# LR1302_LoRaWAN_Gateway_Module_V1_0_868US.net
KiCad netlist of a schematic drawn in EAGLE
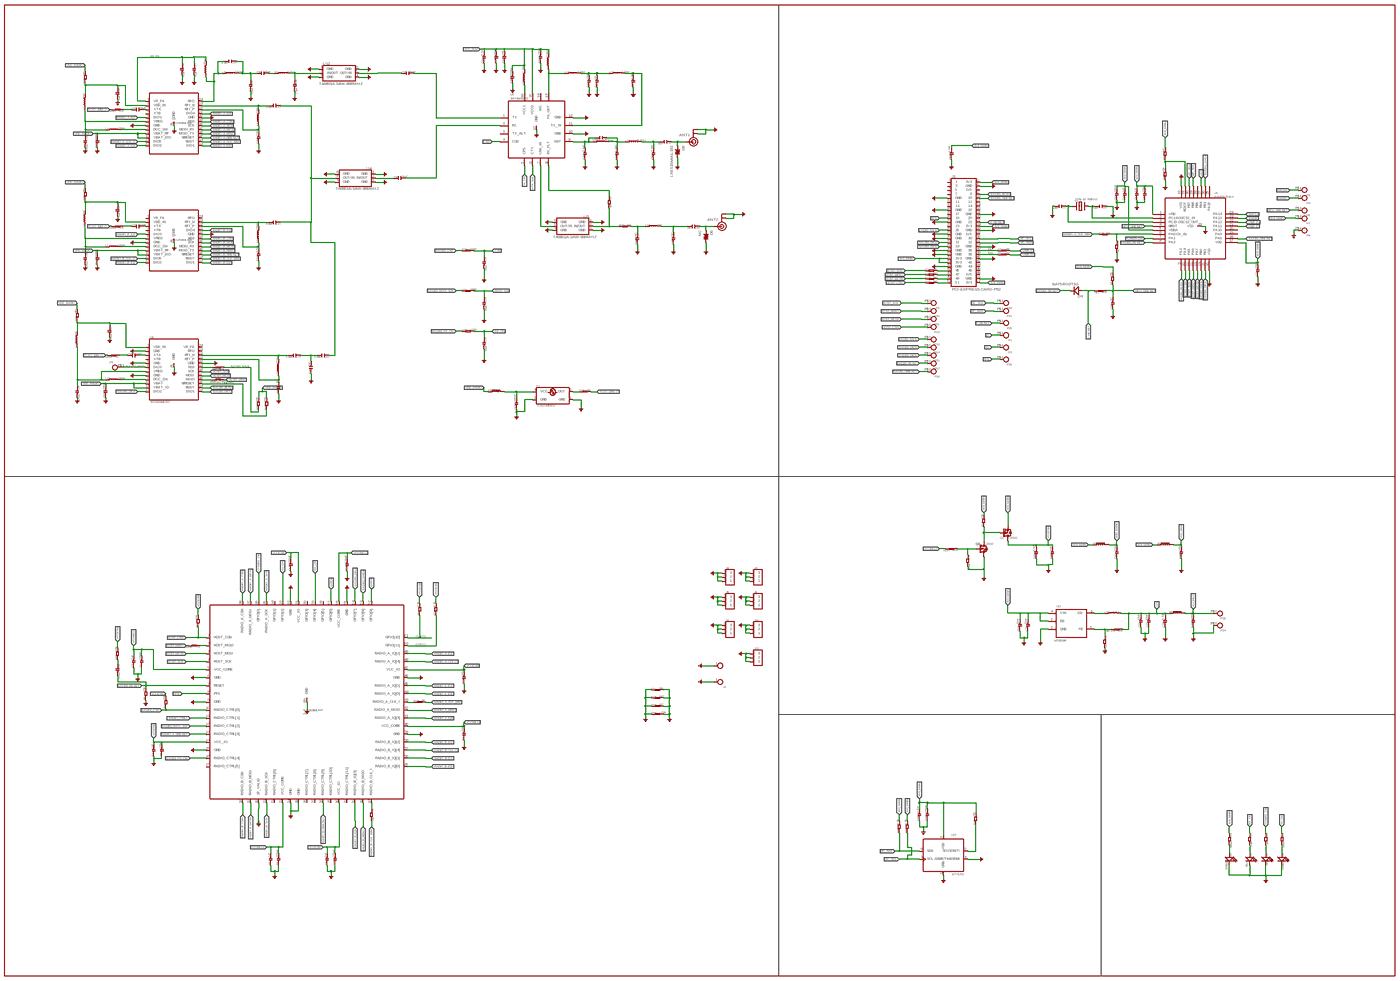
[diagram p0: schematic, sheet 1, overview]
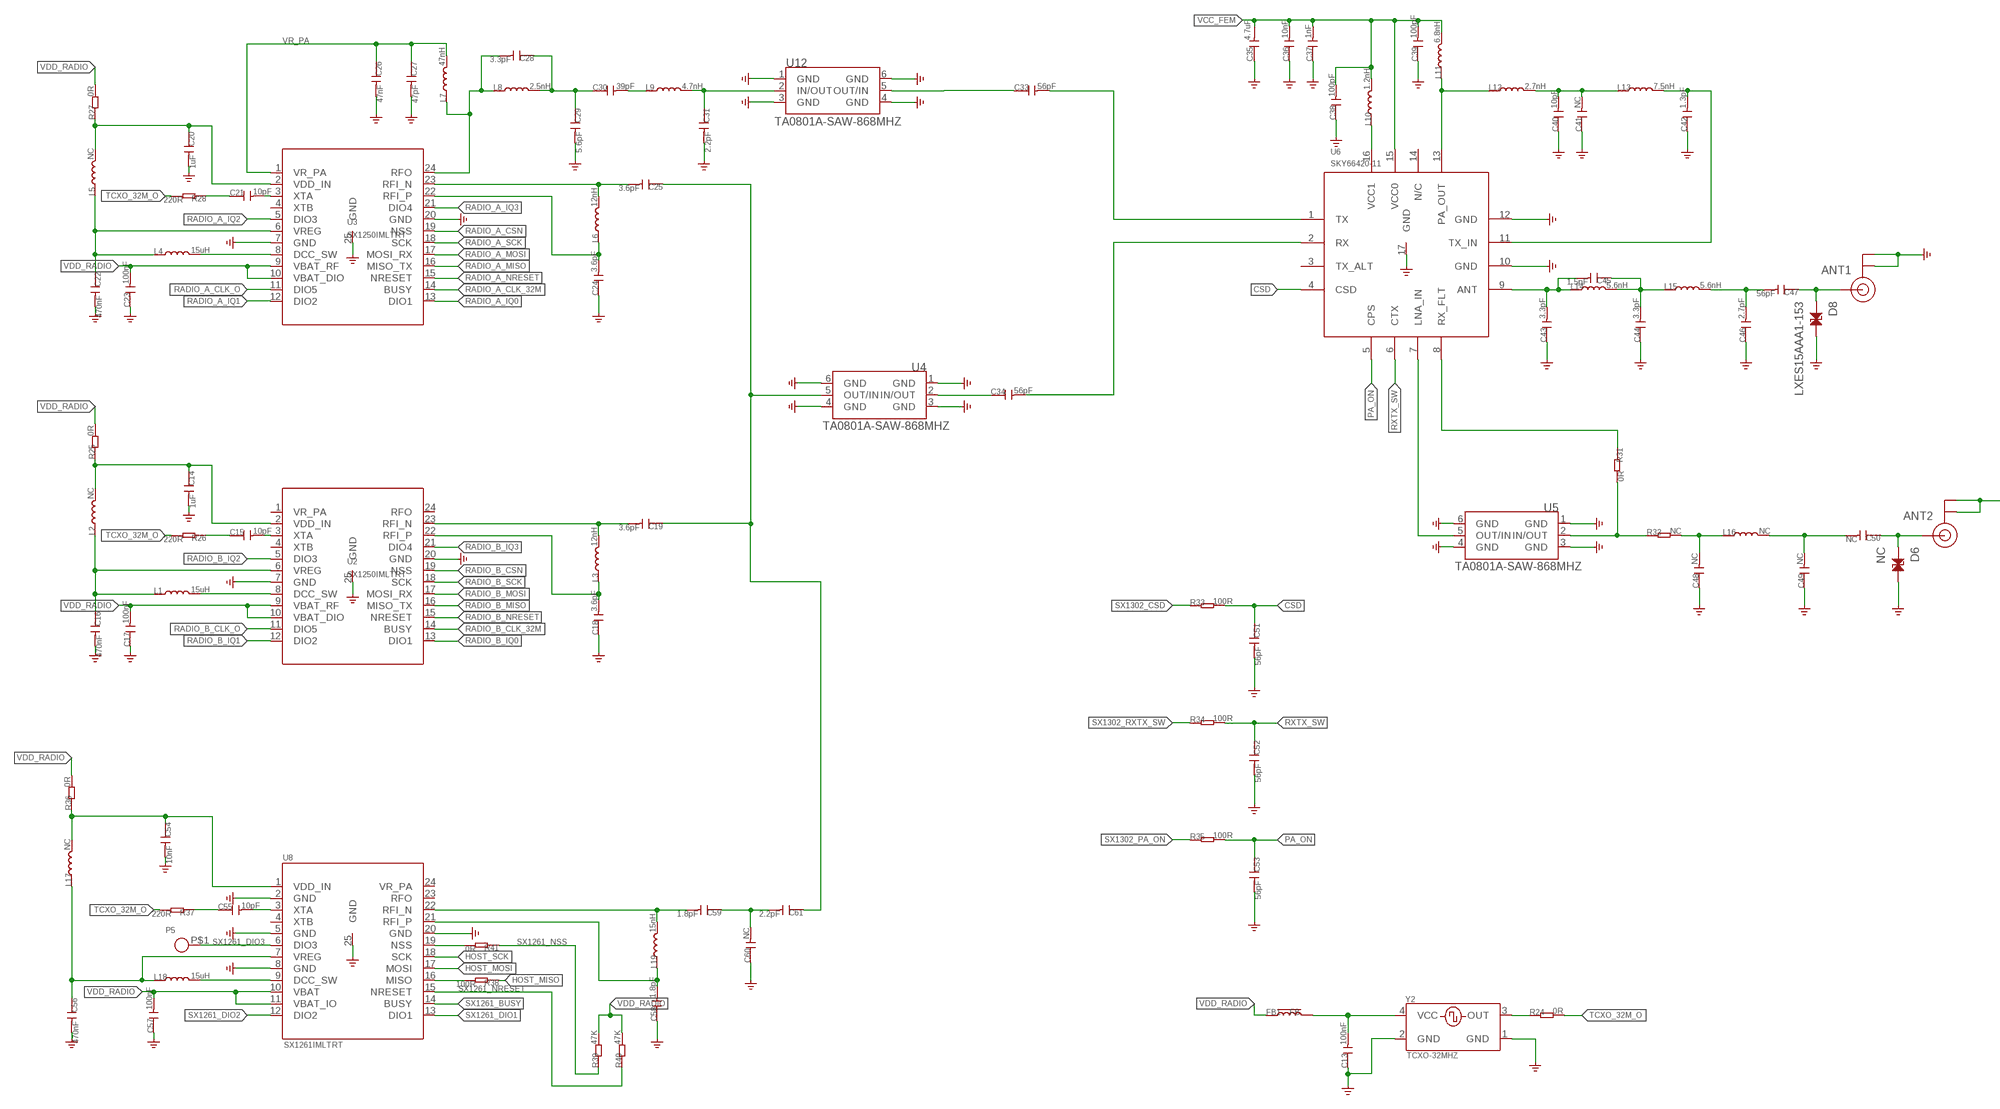
[diagram p1: schematic, sheet 1, part 1 of 4]
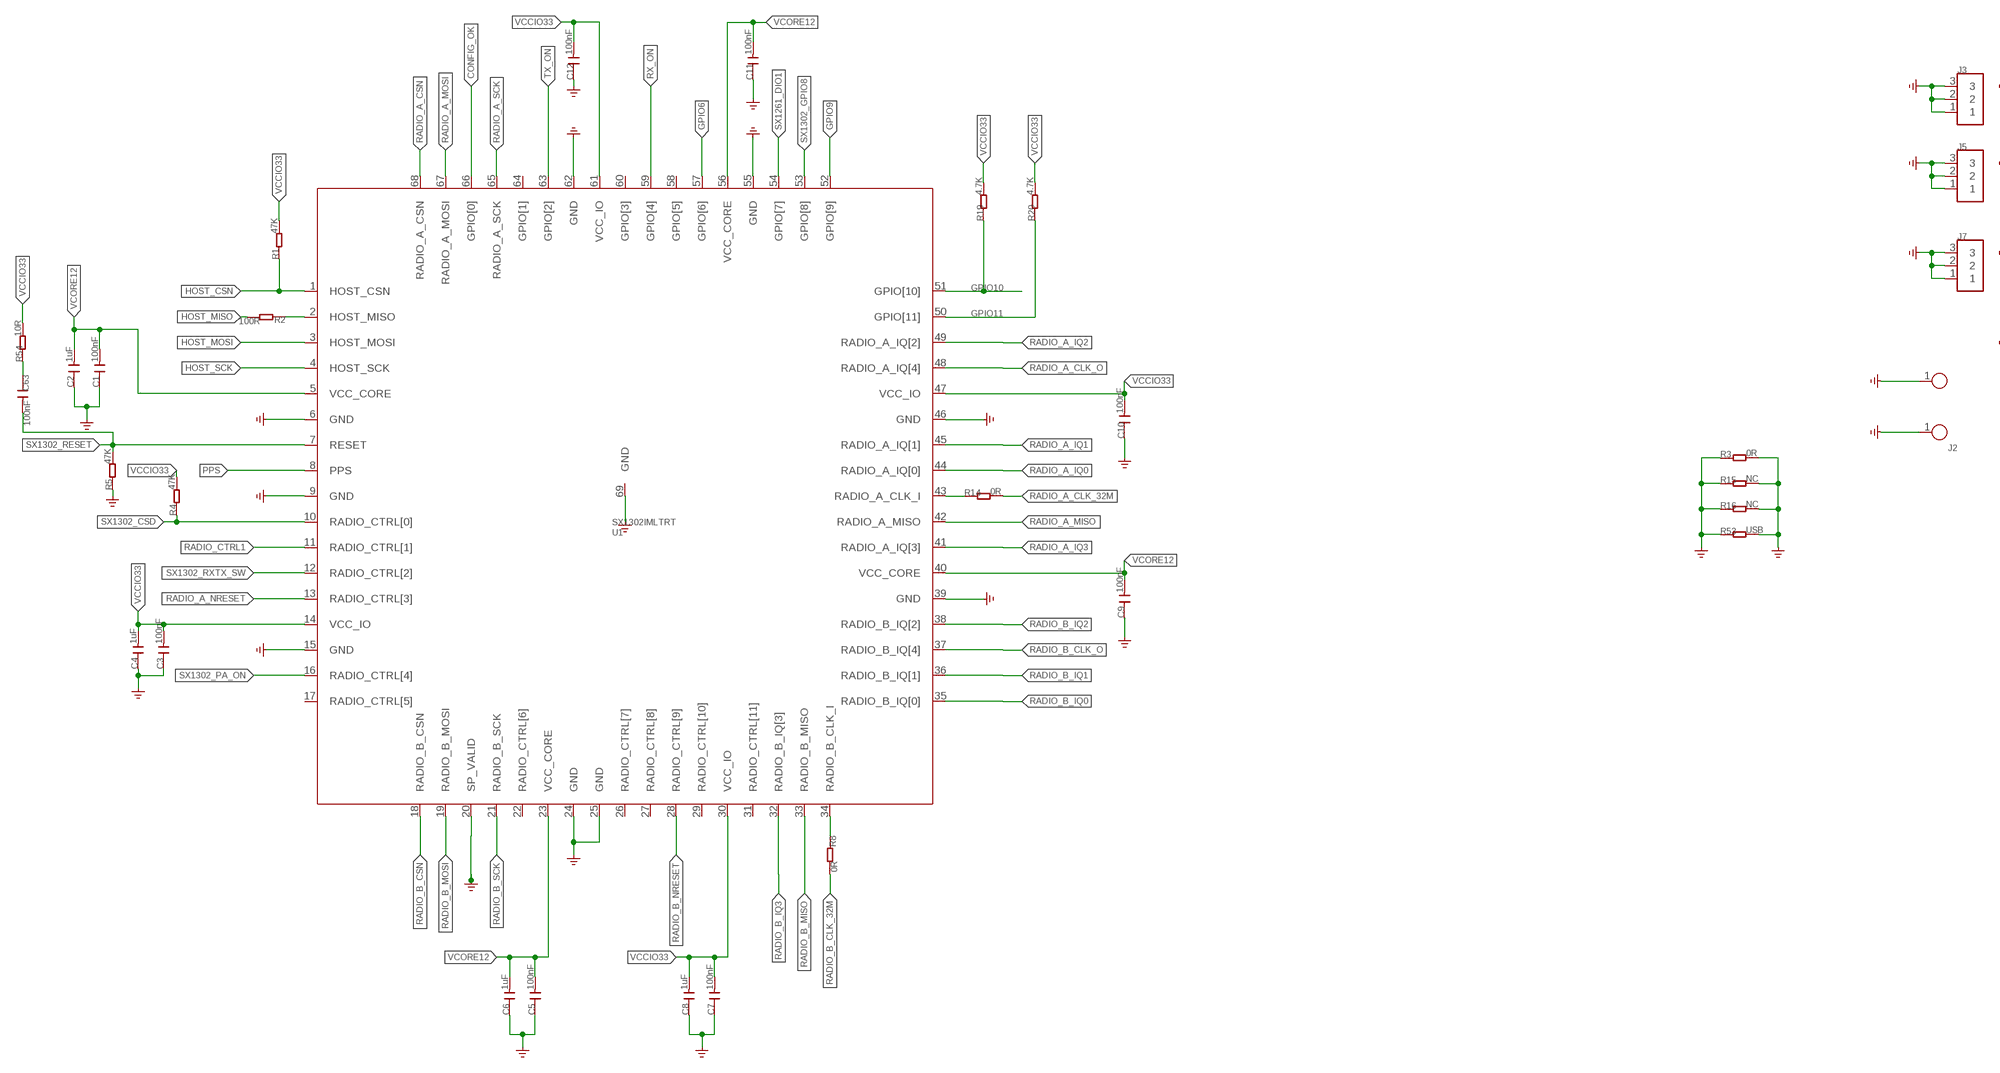
[diagram p2: schematic, sheet 1, part 2 of 4]
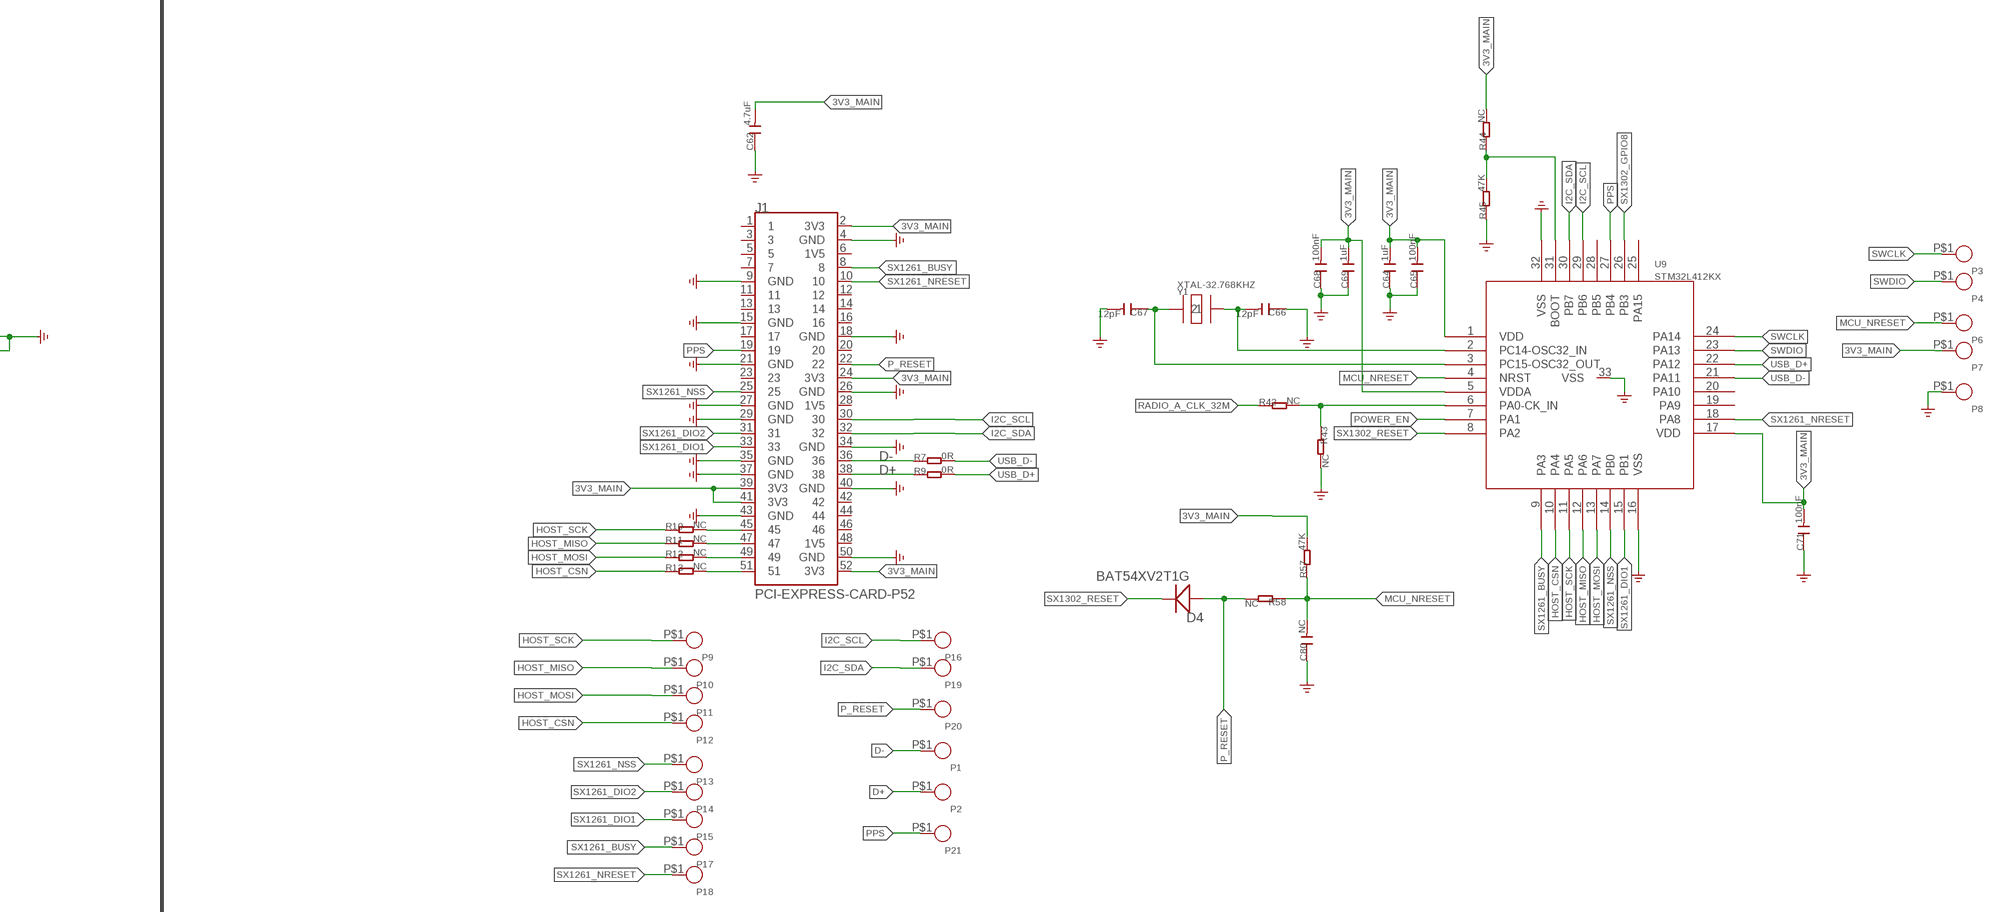
[diagram p3: schematic, sheet 1, part 3 of 4]
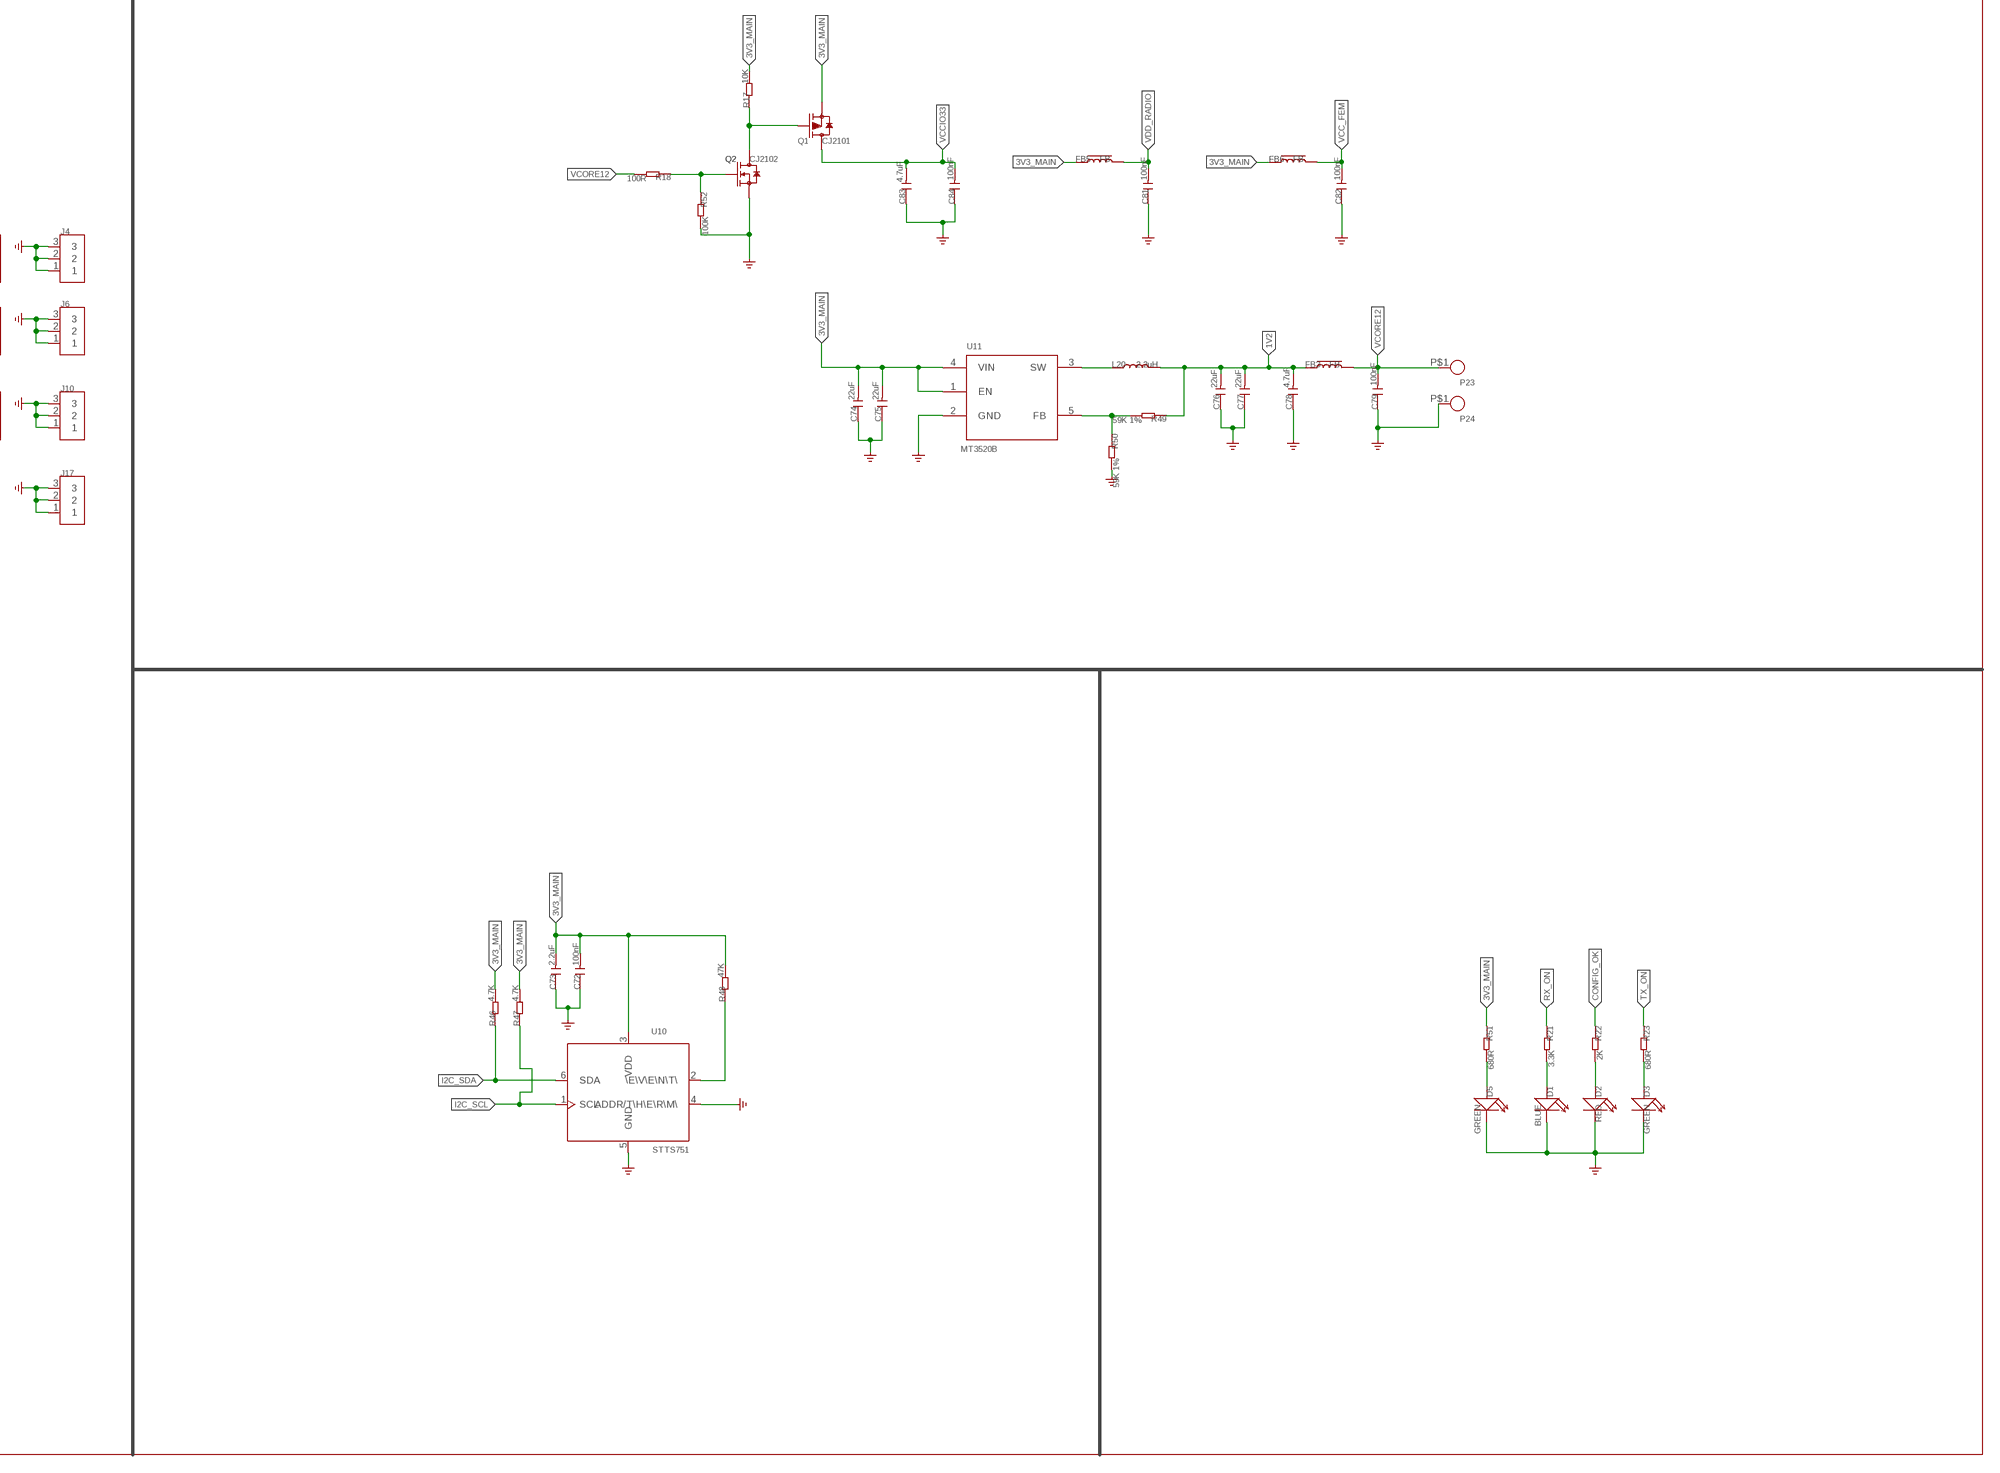
[diagram p4: schematic, sheet 1, part 4 of 4]

(export (version "E")
  (design (tool "Eeschema 10.0.6"))
  (components
    (comp (ref "ANT1")
      (value "U.FL_SMTU.FL-R-SMD")
      (footprint "eagle-import:U.FL-R-SMD")
      (libsource (lib "eagle-import") (part "U.FL_SMTU.FL-R-SMD"))
    )
    (comp (ref "ANT2")
      (value "NC")
      (footprint "eagle-import:U.FL-R-SMD")
      (libsource (lib "eagle-import") (part "U.FL_SMTU.FL-R-SMD"))
    )
    (comp (ref "C1")
      (value "100nF")
      (footprint "eagle-import:C0402")
      (libsource (lib "eagle-import") (part "CAPC0402-1"))
    )
    (comp (ref "C2")
      (value "1uF")
      (footprint "eagle-import:C0402")
      (libsource (lib "eagle-import") (part "CAPC0402-1"))
    )
    (comp (ref "C3")
      (value "100nF")
      (footprint "eagle-import:C0402")
      (libsource (lib "eagle-import") (part "CAPC0402-1"))
    )
    (comp (ref "C4")
      (value "1uF")
      (footprint "eagle-import:C0402")
      (libsource (lib "eagle-import") (part "CAPC0402-1"))
    )
    (comp (ref "C5")
      (value "100nF")
      (footprint "eagle-import:C0402")
      (libsource (lib "eagle-import") (part "CAPC0402-1"))
    )
    (comp (ref "C6")
      (value "1uF")
      (footprint "eagle-import:C0402")
      (libsource (lib "eagle-import") (part "CAPC0402-1"))
    )
    (comp (ref "C7")
      (value "100nF")
      (footprint "eagle-import:C0402")
      (libsource (lib "eagle-import") (part "CAPC0402-1"))
    )
    (comp (ref "C8")
      (value "1uF")
      (footprint "eagle-import:C0402")
      (libsource (lib "eagle-import") (part "CAPC0402-1"))
    )
    (comp (ref "C9")
      (value "100nF")
      (footprint "eagle-import:C0402")
      (libsource (lib "eagle-import") (part "CAPC0402-1"))
    )
    (comp (ref "C10")
      (value "100nF")
      (footprint "eagle-import:C0402")
      (libsource (lib "eagle-import") (part "CAPC0402-1"))
    )
    (comp (ref "C11")
      (value "100nF")
      (footprint "eagle-import:C0402")
      (libsource (lib "eagle-import") (part "CAPC0402-1"))
    )
    (comp (ref "C12")
      (value "100nF")
      (footprint "eagle-import:C0402")
      (libsource (lib "eagle-import") (part "CAPC0402-1"))
    )
    (comp (ref "C13")
      (value "100nF")
      (footprint "eagle-import:C0402")
      (libsource (lib "eagle-import") (part "CAPC0402-1"))
    )
    (comp (ref "C14")
      (value "1uF")
      (footprint "eagle-import:C0402")
      (libsource (lib "eagle-import") (part "CAPC0402-1"))
    )
    (comp (ref "C15")
      (value "10pF")
      (footprint "eagle-import:C0402")
      (libsource (lib "eagle-import") (part "CAPC0402-1"))
    )
    (comp (ref "C16")
      (value "470nF")
      (footprint "eagle-import:C0402")
      (libsource (lib "eagle-import") (part "CAPC0402-1"))
    )
    (comp (ref "C17")
      (value "100nF")
      (footprint "eagle-import:C0402")
      (libsource (lib "eagle-import") (part "CAPC0402-1"))
    )
    (comp (ref "C18")
      (value "3.6pF")
      (footprint "eagle-import:C0402")
      (libsource (lib "eagle-import") (part "CAPC0402-1"))
    )
    (comp (ref "C19")
      (value "3.6pF")
      (footprint "eagle-import:C0402")
      (libsource (lib "eagle-import") (part "CAPC0402-1"))
    )
    (comp (ref "C20")
      (value "1uF")
      (footprint "eagle-import:C0402")
      (libsource (lib "eagle-import") (part "CAPC0402-1"))
    )
    (comp (ref "C21")
      (value "10pF")
      (footprint "eagle-import:C0402")
      (libsource (lib "eagle-import") (part "CAPC0402-1"))
    )
    (comp (ref "C22")
      (value "470nF")
      (footprint "eagle-import:C0402")
      (libsource (lib "eagle-import") (part "CAPC0402-1"))
    )
    (comp (ref "C23")
      (value "100nF")
      (footprint "eagle-import:C0402")
      (libsource (lib "eagle-import") (part "CAPC0402-1"))
    )
    (comp (ref "C24")
      (value "3.6pF")
      (footprint "eagle-import:C0402")
      (libsource (lib "eagle-import") (part "CAPC0402-1"))
    )
    (comp (ref "C25")
      (value "3.6pF")
      (footprint "eagle-import:C0402")
      (libsource (lib "eagle-import") (part "CAPC0402-1"))
    )
    (comp (ref "C26")
      (value "47nF")
      (footprint "eagle-import:C0402")
      (libsource (lib "eagle-import") (part "CAPC0402-1"))
    )
    (comp (ref "C27")
      (value "47pF")
      (footprint "eagle-import:C0402")
      (libsource (lib "eagle-import") (part "CAPC0402-1"))
    )
    (comp (ref "C28")
      (value "3.3pF")
      (footprint "eagle-import:C0402")
      (libsource (lib "eagle-import") (part "CAPC0402-1"))
    )
    (comp (ref "C29")
      (value "5.6pF")
      (footprint "eagle-import:C0402")
      (libsource (lib "eagle-import") (part "CAPC0402-1"))
    )
    (comp (ref "C30")
      (value "39pF")
      (footprint "eagle-import:C0402")
      (libsource (lib "eagle-import") (part "CAPC0402-1"))
    )
    (comp (ref "C31")
      (value "2.2pF")
      (footprint "eagle-import:C0402")
      (libsource (lib "eagle-import") (part "CAPC0402-1"))
    )
    (comp (ref "C33")
      (value "56pF")
      (footprint "eagle-import:C0402")
      (libsource (lib "eagle-import") (part "CAPC0402-1"))
    )
    (comp (ref "C34")
      (value "56pF")
      (footprint "eagle-import:C0402")
      (libsource (lib "eagle-import") (part "CAPC0402-1"))
    )
    (comp (ref "C35")
      (value "4.7uF")
      (footprint "eagle-import:C0603")
      (libsource (lib "eagle-import") (part "CAP"))
    )
    (comp (ref "C36")
      (value "10nF")
      (footprint "eagle-import:C0402")
      (libsource (lib "eagle-import") (part "CAPC0402-1"))
    )
    (comp (ref "C37")
      (value "1nF")
      (footprint "eagle-import:C0402")
      (libsource (lib "eagle-import") (part "CAPC0402-1"))
    )
    (comp (ref "C38")
      (value "100pF")
      (footprint "eagle-import:C0402")
      (libsource (lib "eagle-import") (part "CAPC0402-1"))
    )
    (comp (ref "C39")
      (value "100pF")
      (footprint "eagle-import:C0402")
      (libsource (lib "eagle-import") (part "CAPC0402-1"))
    )
    (comp (ref "C40")
      (value "10pF")
      (footprint "eagle-import:C0402")
      (libsource (lib "eagle-import") (part "CAPC0402-1"))
    )
    (comp (ref "C41")
      (value "NC")
      (footprint "eagle-import:C0402")
      (libsource (lib "eagle-import") (part "CAPC0402-1"))
    )
    (comp (ref "C42")
      (value "1.3pF")
      (footprint "eagle-import:C0402")
      (libsource (lib "eagle-import") (part "CAPC0402-1"))
    )
    (comp (ref "C43")
      (value "3.3pF")
      (footprint "eagle-import:C0402")
      (libsource (lib "eagle-import") (part "CAPC0402-1"))
    )
    (comp (ref "C44")
      (value "3.3pF")
      (footprint "eagle-import:C0402")
      (libsource (lib "eagle-import") (part "CAPC0402-1"))
    )
    (comp (ref "C45")
      (value "1.5pF")
      (footprint "eagle-import:C0402")
      (libsource (lib "eagle-import") (part "CAPC0402-1"))
    )
    (comp (ref "C46")
      (value "2.7pF")
      (footprint "eagle-import:C0402")
      (libsource (lib "eagle-import") (part "CAPC0402-1"))
    )
    (comp (ref "C47")
      (value "56pF")
      (footprint "eagle-import:C0402")
      (libsource (lib "eagle-import") (part "CAPC0402-1"))
    )
    (comp (ref "C48")
      (value "NC")
      (footprint "eagle-import:C0402")
      (libsource (lib "eagle-import") (part "CAPC0402-1"))
    )
    (comp (ref "C49")
      (value "NC")
      (footprint "eagle-import:C0402")
      (libsource (lib "eagle-import") (part "CAPC0402-1"))
    )
    (comp (ref "C50")
      (value "NC")
      (footprint "eagle-import:C0402")
      (libsource (lib "eagle-import") (part "CAPC0402-1"))
    )
    (comp (ref "C51")
      (value "56pF")
      (footprint "eagle-import:C0402")
      (libsource (lib "eagle-import") (part "CAPC0402-1"))
    )
    (comp (ref "C52")
      (value "56pF")
      (footprint "eagle-import:C0402")
      (libsource (lib "eagle-import") (part "CAPC0402-1"))
    )
    (comp (ref "C53")
      (value "56pF")
      (footprint "eagle-import:C0402")
      (libsource (lib "eagle-import") (part "CAPC0402-1"))
    )
    (comp (ref "C54")
      (value "10nF")
      (footprint "eagle-import:C0402")
      (libsource (lib "eagle-import") (part "CAPC0402-1"))
    )
    (comp (ref "C55")
      (value "10pF")
      (footprint "eagle-import:C0402")
      (libsource (lib "eagle-import") (part "CAPC0402-1"))
    )
    (comp (ref "C56")
      (value "470nF")
      (footprint "eagle-import:C0402")
      (libsource (lib "eagle-import") (part "CAPC0402-1"))
    )
    (comp (ref "C57")
      (value "100nF")
      (footprint "eagle-import:C0402")
      (libsource (lib "eagle-import") (part "CAPC0402-1"))
    )
    (comp (ref "C58")
      (value "1.8pF")
      (footprint "eagle-import:C0402")
      (libsource (lib "eagle-import") (part "CAPC0402-1"))
    )
    (comp (ref "C59")
      (value "1.8pF")
      (footprint "eagle-import:C0402")
      (libsource (lib "eagle-import") (part "CAPC0402-1"))
    )
    (comp (ref "C60")
      (value "NC")
      (footprint "eagle-import:C0402")
      (libsource (lib "eagle-import") (part "CAPC0402-1"))
    )
    (comp (ref "C61")
      (value "2.2pF")
      (footprint "eagle-import:C0402")
      (libsource (lib "eagle-import") (part "CAPC0402-1"))
    )
    (comp (ref "C62")
      (value "4.7uF")
      (footprint "eagle-import:C0603")
      (libsource (lib "eagle-import") (part "CAP"))
    )
    (comp (ref "C63")
      (value "100nF")
      (footprint "eagle-import:C0402")
      (libsource (lib "eagle-import") (part "CAPC0402-1"))
    )
    (comp (ref "C64")
      (value "1uF")
      (footprint "eagle-import:C0402")
      (libsource (lib "eagle-import") (part "CAPC0402-1"))
    )
    (comp (ref "C65")
      (value "100nF")
      (footprint "eagle-import:C0402")
      (libsource (lib "eagle-import") (part "CAPC0402-1"))
    )
    (comp (ref "C66")
      (value "12pF")
      (footprint "eagle-import:C0402")
      (libsource (lib "eagle-import") (part "CAPC0402-1"))
    )
    (comp (ref "C67")
      (value "12pF")
      (footprint "eagle-import:C0402")
      (libsource (lib "eagle-import") (part "CAPC0402-1"))
    )
    (comp (ref "C68")
      (value "100nF")
      (footprint "eagle-import:C0402")
      (libsource (lib "eagle-import") (part "CAPC0402-1"))
    )
    (comp (ref "C69")
      (value "1uF")
      (footprint "eagle-import:C0402")
      (libsource (lib "eagle-import") (part "CAPC0402-1"))
    )
    (comp (ref "C71")
      (value "100nF")
      (footprint "eagle-import:C0402")
      (libsource (lib "eagle-import") (part "CAPC0402-1"))
    )
    (comp (ref "C72")
      (value "100nF")
      (footprint "eagle-import:C0402")
      (libsource (lib "eagle-import") (part "CAPC0402-1"))
    )
    (comp (ref "C73")
      (value "2.2uF")
      (footprint "eagle-import:C0402")
      (libsource (lib "eagle-import") (part "CAPC0402-1"))
    )
    (comp (ref "C74")
      (value "22uF")
      (footprint "eagle-import:C0603")
      (libsource (lib "eagle-import") (part "CAP"))
    )
    (comp (ref "C75")
      (value "22uF")
      (footprint "eagle-import:C0603")
      (libsource (lib "eagle-import") (part "CAP"))
    )
    (comp (ref "C76")
      (value "22uF")
      (footprint "eagle-import:C0603")
      (libsource (lib "eagle-import") (part "CAP"))
    )
    (comp (ref "C77")
      (value "22uF")
      (footprint "eagle-import:C0603")
      (libsource (lib "eagle-import") (part "CAP"))
    )
    (comp (ref "C78")
      (value "4.7uF")
      (footprint "eagle-import:C0603")
      (libsource (lib "eagle-import") (part "CAP"))
    )
    (comp (ref "C79")
      (value "100nF")
      (footprint "eagle-import:C0402")
      (libsource (lib "eagle-import") (part "CAPC0402-1"))
    )
    (comp (ref "C80")
      (value "NC")
      (footprint "eagle-import:C0402")
      (libsource (lib "eagle-import") (part "CAPC0402-1"))
    )
    (comp (ref "C81")
      (value "100nF")
      (footprint "eagle-import:C0402")
      (libsource (lib "eagle-import") (part "CAPC0402-1"))
    )
    (comp (ref "C82")
      (value "100nF")
      (footprint "eagle-import:C0402")
      (libsource (lib "eagle-import") (part "CAPC0402-1"))
    )
    (comp (ref "C83")
      (value "4.7uF")
      (footprint "eagle-import:C0603")
      (libsource (lib "eagle-import") (part "CAP"))
    )
    (comp (ref "C84")
      (value "100nF")
      (footprint "eagle-import:C0402")
      (libsource (lib "eagle-import") (part "CAPC0402-1"))
    )
    (comp (ref "D1")
      (value "BLUE")
      (footprint "eagle-import:LED-0402")
      (libsource (lib "eagle-import") (part "LED-SMT"))
    )
    (comp (ref "D2")
      (value "RED")
      (footprint "eagle-import:LED-0402")
      (libsource (lib "eagle-import") (part "LED-SMT"))
    )
    (comp (ref "D3")
      (value "GREEN")
      (footprint "eagle-import:LED-0402")
      (libsource (lib "eagle-import") (part "LED-SMT"))
    )
    (comp (ref "D4")
      (value "BAT54XV2T1G")
      (footprint "eagle-import:D_SOD523")
      (libsource (lib "eagle-import") (part "DIODE0603"))
    )
    (comp (ref "D5")
      (value "GREEN")
      (footprint "eagle-import:LED-0402")
      (libsource (lib "eagle-import") (part "LED-SMT"))
    )
    (comp (ref "D6")
      (value "NC")
      (footprint "eagle-import:D0402")
      (libsource (lib "eagle-import") (part "PESD0402"))
    )
    (comp (ref "D8")
      (value "LXES15AAA1-153")
      (footprint "eagle-import:D0402")
      (libsource (lib "eagle-import") (part "PESD0402"))
    )
    (comp (ref "FB1")
      (value "FB")
      (footprint "eagle-import:L0402")
      (libsource (lib "eagle-import") (part "FB"))
    )
    (comp (ref "FB3")
      (value "FB")
      (footprint "eagle-import:L0402")
      (libsource (lib "eagle-import") (part "FB"))
    )
    (comp (ref "FB5")
      (value "FB")
      (footprint "eagle-import:L0402")
      (libsource (lib "eagle-import") (part "FB"))
    )
    (comp (ref "FB6")
      (value "FB")
      (footprint "eagle-import:L0402")
      (libsource (lib "eagle-import") (part "FB"))
    )
    (comp (ref "J1")
      (value "PCI-EXPRESS-CARD-P52")
      (footprint "eagle-import:PCIE-MINI-S52")
      (libsource (lib "eagle-import") (part "PCI-EXPRESS-CARD-P52"))
    )
    (comp (ref "J2")
      (value "PAD-THO-2.65MM")
      (footprint "eagle-import:PAD-THO-2.6_5MM")
      (libsource (lib "eagle-import") (part "PAD-THO-2.65MM"))
    )
    (comp (ref "J3")
      (value "PBJ-ICSRC6508-SMD")
      (footprint "eagle-import:PBJ-ICSRC6508-SMD")
      (libsource (lib "eagle-import") (part "PBJ-ICSRC6508-SMD"))
    )
    (comp (ref "J4")
      (value "PBJ-ICSRC6508-SMD")
      (footprint "eagle-import:PBJ-ICSRC6508-SMD")
      (libsource (lib "eagle-import") (part "PBJ-ICSRC6508-SMD"))
    )
    (comp (ref "J5")
      (value "PBJ-ICSRC6508-SMD")
      (footprint "eagle-import:PBJ-ICSRC6508-SMD")
      (libsource (lib "eagle-import") (part "PBJ-ICSRC6508-SMD"))
    )
    (comp (ref "J6")
      (value "PBJ-ICSRC6508-SMD")
      (footprint "eagle-import:PBJ-ICSRC6508-SMD")
      (libsource (lib "eagle-import") (part "PBJ-ICSRC6508-SMD"))
    )
    (comp (ref "J7")
      (value "PBJ-ICSRC6508-SMD")
      (footprint "eagle-import:PBJ-ICSRC6508-SMD")
      (libsource (lib "eagle-import") (part "PBJ-ICSRC6508-SMD"))
    )
    (comp (ref "J10")
      (value "PBJ-ICSRC6508-SMD")
      (footprint "eagle-import:PBJ-ICSRC6508-SMD")
      (libsource (lib "eagle-import") (part "PBJ-ICSRC6508-SMD"))
    )
    (comp (ref "J11")
      (value "PAD-THO-2.65MM")
      (footprint "eagle-import:PAD-THO-2.6_5MM")
      (libsource (lib "eagle-import") (part "PAD-THO-2.65MM"))
    )
    (comp (ref "J17")
      (value "PBJ-ICSRC6508-SMD")
      (footprint "eagle-import:PBJ-ICSRC6508-SMD")
      (libsource (lib "eagle-import") (part "PBJ-ICSRC6508-SMD"))
    )
    (comp (ref "L1")
      (value "15uH")
      (footprint "eagle-import:L0805")
      (libsource (lib "eagle-import") (part "L0805"))
    )
    (comp (ref "L2")
      (value "NC")
      (footprint "eagle-import:L0402")
      (libsource (lib "eagle-import") (part "L0402"))
    )
    (comp (ref "L3")
      (value "12nH")
      (footprint "eagle-import:L0402")
      (libsource (lib "eagle-import") (part "L0402"))
    )
    (comp (ref "L4")
      (value "15uH")
      (footprint "eagle-import:L0805")
      (libsource (lib "eagle-import") (part "L0805"))
    )
    (comp (ref "L5")
      (value "NC")
      (footprint "eagle-import:L0402")
      (libsource (lib "eagle-import") (part "L0402"))
    )
    (comp (ref "L6")
      (value "12nH")
      (footprint "eagle-import:L0402")
      (libsource (lib "eagle-import") (part "L0402"))
    )
    (comp (ref "L7")
      (value "47nH")
      (footprint "eagle-import:L0402")
      (libsource (lib "eagle-import") (part "L0402"))
    )
    (comp (ref "L8")
      (value "2.5nH")
      (footprint "eagle-import:L0402")
      (libsource (lib "eagle-import") (part "L0402"))
    )
    (comp (ref "L9")
      (value "4.7nH")
      (footprint "eagle-import:L0402")
      (libsource (lib "eagle-import") (part "L0402"))
    )
    (comp (ref "L10")
      (value "1.2nH")
      (footprint "eagle-import:L0402")
      (libsource (lib "eagle-import") (part "L0402"))
    )
    (comp (ref "L11")
      (value "6.8nH")
      (footprint "eagle-import:L0402")
      (libsource (lib "eagle-import") (part "L0402"))
    )
    (comp (ref "L12")
      (value "2.7nH")
      (footprint "eagle-import:L0402")
      (libsource (lib "eagle-import") (part "L0402"))
    )
    (comp (ref "L13")
      (value "7.5nH")
      (footprint "eagle-import:L0402")
      (libsource (lib "eagle-import") (part "L0402"))
    )
    (comp (ref "L14")
      (value "5.6nH")
      (footprint "eagle-import:L0402")
      (libsource (lib "eagle-import") (part "L0402"))
    )
    (comp (ref "L15")
      (value "5.6nH")
      (footprint "eagle-import:L0402")
      (libsource (lib "eagle-import") (part "L0402"))
    )
    (comp (ref "L16")
      (value "NC")
      (footprint "eagle-import:L0402")
      (libsource (lib "eagle-import") (part "L0402"))
    )
    (comp (ref "L17")
      (value "NC")
      (footprint "eagle-import:L0402")
      (libsource (lib "eagle-import") (part "L0402"))
    )
    (comp (ref "L18")
      (value "15uH")
      (footprint "eagle-import:L0805")
      (libsource (lib "eagle-import") (part "L0805"))
    )
    (comp (ref "L19")
      (value "15nH")
      (footprint "eagle-import:L0402")
      (libsource (lib "eagle-import") (part "L0402"))
    )
    (comp (ref "L20")
      (value "2.2uH")
      (footprint "eagle-import:L3015_SMD")
      (libsource (lib "eagle-import") (part "L"))
    )
    (comp (ref "P1")
      (value "TEST_PADPAD-1.0MM")
      (footprint "eagle-import:TEST_PAD-1.0MM")
      (libsource (lib "eagle-import") (part "TEST_PADPAD-1.0MM"))
    )
    (comp (ref "P2")
      (value "TEST_PADPAD-1.0MM")
      (footprint "eagle-import:TEST_PAD-1.0MM")
      (libsource (lib "eagle-import") (part "TEST_PADPAD-1.0MM"))
    )
    (comp (ref "P3")
      (value "TEST_PADPAD-1.0MM")
      (footprint "eagle-import:TEST_PAD-1.0MM")
      (libsource (lib "eagle-import") (part "TEST_PADPAD-1.0MM"))
    )
    (comp (ref "P4")
      (value "TEST_PADPAD-1.0MM")
      (footprint "eagle-import:TEST_PAD-1.0MM")
      (libsource (lib "eagle-import") (part "TEST_PADPAD-1.0MM"))
    )
    (comp (ref "P5")
      (value "TEST_PADPAD-1.0MM")
      (footprint "eagle-import:TEST_PAD-1.0MM")
      (libsource (lib "eagle-import") (part "TEST_PADPAD-1.0MM"))
    )
    (comp (ref "P6")
      (value "TEST_PADPAD-1.0MM")
      (footprint "eagle-import:TEST_PAD-1.0MM")
      (libsource (lib "eagle-import") (part "TEST_PADPAD-1.0MM"))
    )
    (comp (ref "P7")
      (value "TEST_PADPAD-1.0MM")
      (footprint "eagle-import:TEST_PAD-1.0MM")
      (libsource (lib "eagle-import") (part "TEST_PADPAD-1.0MM"))
    )
    (comp (ref "P8")
      (value "TEST_PADPAD-1.0MM")
      (footprint "eagle-import:TEST_PAD-1.0MM")
      (libsource (lib "eagle-import") (part "TEST_PADPAD-1.0MM"))
    )
    (comp (ref "P9")
      (value "TEST_PADPAD-1.0MM")
      (footprint "eagle-import:TEST_PAD-1.0MM")
      (libsource (lib "eagle-import") (part "TEST_PADPAD-1.0MM"))
    )
    (comp (ref "P10")
      (value "TEST_PADPAD-1.0MM")
      (footprint "eagle-import:TEST_PAD-1.0MM")
      (libsource (lib "eagle-import") (part "TEST_PADPAD-1.0MM"))
    )
    (comp (ref "P11")
      (value "TEST_PADPAD-1.0MM")
      (footprint "eagle-import:TEST_PAD-1.0MM")
      (libsource (lib "eagle-import") (part "TEST_PADPAD-1.0MM"))
    )
    (comp (ref "P12")
      (value "TEST_PADPAD-1.0MM")
      (footprint "eagle-import:TEST_PAD-1.0MM")
      (libsource (lib "eagle-import") (part "TEST_PADPAD-1.0MM"))
    )
    (comp (ref "P13")
      (value "TEST_PADPAD-1.0MM")
      (footprint "eagle-import:TEST_PAD-1.0MM")
      (libsource (lib "eagle-import") (part "TEST_PADPAD-1.0MM"))
    )
    (comp (ref "P14")
      (value "TEST_PADPAD-1.0MM")
      (footprint "eagle-import:TEST_PAD-1.0MM")
      (libsource (lib "eagle-import") (part "TEST_PADPAD-1.0MM"))
    )
    (comp (ref "P15")
      (value "TEST_PADPAD-1.0MM")
      (footprint "eagle-import:TEST_PAD-1.0MM")
      (libsource (lib "eagle-import") (part "TEST_PADPAD-1.0MM"))
    )
    (comp (ref "P16")
      (value "TEST_PADPAD-1.0MM")
      (footprint "eagle-import:TEST_PAD-1.0MM")
      (libsource (lib "eagle-import") (part "TEST_PADPAD-1.0MM"))
    )
    (comp (ref "P17")
      (value "TEST_PADPAD-1.0MM")
      (footprint "eagle-import:TEST_PAD-1.0MM")
      (libsource (lib "eagle-import") (part "TEST_PADPAD-1.0MM"))
    )
    (comp (ref "P18")
      (value "TEST_PADPAD-1.0MM")
      (footprint "eagle-import:TEST_PAD-1.0MM")
      (libsource (lib "eagle-import") (part "TEST_PADPAD-1.0MM"))
    )
    (comp (ref "P19")
      (value "TEST_PADPAD-1.0MM")
      (footprint "eagle-import:TEST_PAD-1.0MM")
      (libsource (lib "eagle-import") (part "TEST_PADPAD-1.0MM"))
    )
    (comp (ref "P20")
      (value "TEST_PADPAD-1.0MM")
      (footprint "eagle-import:TEST_PAD-1.0MM")
      (libsource (lib "eagle-import") (part "TEST_PADPAD-1.0MM"))
    )
    (comp (ref "P21")
      (value "TEST_PADPAD-1.0MM")
      (footprint "eagle-import:TEST_PAD-1.0MM")
      (libsource (lib "eagle-import") (part "TEST_PADPAD-1.0MM"))
    )
    (comp (ref "P23")
      (value "TEST_PADPAD-1.0MM")
      (footprint "eagle-import:TEST_PAD-1.0MM")
      (libsource (lib "eagle-import") (part "TEST_PADPAD-1.0MM"))
    )
    (comp (ref "P24")
      (value "TEST_PADPAD-1.0MM")
      (footprint "eagle-import:TEST_PAD-1.0MM")
      (libsource (lib "eagle-import") (part "TEST_PADPAD-1.0MM"))
    )
    (comp (ref "Q1")
      (value "CJ2101")
      (footprint "eagle-import:MOS_SOT323")
      (libsource (lib "eagle-import") (part "MOSFET-P"))
    )
    (comp (ref "Q2")
      (value "CJ2102")
      (footprint "eagle-import:MOS_SOT323")
      (libsource (lib "eagle-import") (part "MOSFET-NSI1304BDL"))
    )
    (comp (ref "R1")
      (value "47K")
      (footprint "eagle-import:R0402")
      (libsource (lib "eagle-import") (part "RES-0402"))
    )
    (comp (ref "R2")
      (value "100R")
      (footprint "eagle-import:R0402")
      (libsource (lib "eagle-import") (part "RES-0402"))
    )
    (comp (ref "R3")
      (value "0R")
      (footprint "eagle-import:R0402")
      (libsource (lib "eagle-import") (part "RES-0402"))
    )
    (comp (ref "R4")
      (value "47K")
      (footprint "eagle-import:R0402")
      (libsource (lib "eagle-import") (part "RES-0402"))
    )
    (comp (ref "R5")
      (value "47K")
      (footprint "eagle-import:R0402")
      (libsource (lib "eagle-import") (part "RES-0402"))
    )
    (comp (ref "R7")
      (value "0R")
      (footprint "eagle-import:R0402")
      (libsource (lib "eagle-import") (part "RES-0402"))
    )
    (comp (ref "R8")
      (value "0R")
      (footprint "eagle-import:R0402")
      (libsource (lib "eagle-import") (part "RES-0402"))
    )
    (comp (ref "R9")
      (value "0R")
      (footprint "eagle-import:R0402")
      (libsource (lib "eagle-import") (part "RES-0402"))
    )
    (comp (ref "R10")
      (value "NC")
      (footprint "eagle-import:R0402")
      (libsource (lib "eagle-import") (part "RES-0402"))
    )
    (comp (ref "R11")
      (value "NC")
      (footprint "eagle-import:R0402")
      (libsource (lib "eagle-import") (part "RES-0402"))
    )
    (comp (ref "R12")
      (value "NC")
      (footprint "eagle-import:R0402")
      (libsource (lib "eagle-import") (part "RES-0402"))
    )
    (comp (ref "R13")
      (value "NC")
      (footprint "eagle-import:R0402")
      (libsource (lib "eagle-import") (part "RES-0402"))
    )
    (comp (ref "R14")
      (value "0R")
      (footprint "eagle-import:R0402")
      (libsource (lib "eagle-import") (part "RES-0402"))
    )
    (comp (ref "R15")
      (value "NC")
      (footprint "eagle-import:R0402")
      (libsource (lib "eagle-import") (part "RES-0402"))
    )
    (comp (ref "R16")
      (value "NC")
      (footprint "eagle-import:R0402")
      (libsource (lib "eagle-import") (part "RES-0402"))
    )
    (comp (ref "R17")
      (value "10K")
      (footprint "eagle-import:R0402")
      (libsource (lib "eagle-import") (part "RES-0402"))
    )
    (comp (ref "R18")
      (value "100R")
      (footprint "eagle-import:R0402")
      (libsource (lib "eagle-import") (part "RES-0402"))
    )
    (comp (ref "R19")
      (value "4.7K")
      (footprint "eagle-import:R0402")
      (libsource (lib "eagle-import") (part "RES-0402"))
    )
    (comp (ref "R20")
      (value "4.7K")
      (footprint "eagle-import:R0402")
      (libsource (lib "eagle-import") (part "RES-0402"))
    )
    (comp (ref "R21")
      (value "3.3K")
      (footprint "eagle-import:R0402")
      (libsource (lib "eagle-import") (part "RES-0402"))
    )
    (comp (ref "R22")
      (value "2K")
      (footprint "eagle-import:R0402")
      (libsource (lib "eagle-import") (part "RES-0402"))
    )
    (comp (ref "R23")
      (value "680R")
      (footprint "eagle-import:R0402")
      (libsource (lib "eagle-import") (part "RES-0402"))
    )
    (comp (ref "R24")
      (value "0R")
      (footprint "eagle-import:R0402")
      (libsource (lib "eagle-import") (part "RES-0402"))
    )
    (comp (ref "R25")
      (value "0R")
      (footprint "eagle-import:R0402")
      (libsource (lib "eagle-import") (part "RES-0402"))
    )
    (comp (ref "R26")
      (value "220R")
      (footprint "eagle-import:R0402")
      (libsource (lib "eagle-import") (part "RES-0402"))
    )
    (comp (ref "R27")
      (value "0R")
      (footprint "eagle-import:R0402")
      (libsource (lib "eagle-import") (part "RES-0402"))
    )
    (comp (ref "R28")
      (value "220R")
      (footprint "eagle-import:R0402")
      (libsource (lib "eagle-import") (part "RES-0402"))
    )
    (comp (ref "R31")
      (value "0R")
      (footprint "eagle-import:R0402")
      (libsource (lib "eagle-import") (part "RES-0402"))
    )
    (comp (ref "R32")
      (value "NC")
      (footprint "eagle-import:R0402")
      (libsource (lib "eagle-import") (part "RES-0402"))
    )
    (comp (ref "R33")
      (value "100R")
      (footprint "eagle-import:R0402")
      (libsource (lib "eagle-import") (part "RES-0402"))
    )
    (comp (ref "R34")
      (value "100R")
      (footprint "eagle-import:R0402")
      (libsource (lib "eagle-import") (part "RES-0402"))
    )
    (comp (ref "R35")
      (value "100R")
      (footprint "eagle-import:R0402")
      (libsource (lib "eagle-import") (part "RES-0402"))
    )
    (comp (ref "R36")
      (value "0R")
      (footprint "eagle-import:R0402")
      (libsource (lib "eagle-import") (part "RES-0402"))
    )
    (comp (ref "R37")
      (value "220R")
      (footprint "eagle-import:R0402")
      (libsource (lib "eagle-import") (part "RES-0402"))
    )
    (comp (ref "R38")
      (value "100R")
      (footprint "eagle-import:R0402")
      (libsource (lib "eagle-import") (part "RES-0402"))
    )
    (comp (ref "R39")
      (value "47K")
      (footprint "eagle-import:R0402")
      (libsource (lib "eagle-import") (part "RES-0402"))
    )
    (comp (ref "R40")
      (value "47K")
      (footprint "eagle-import:R0402")
      (libsource (lib "eagle-import") (part "RES-0402"))
    )
    (comp (ref "R41")
      (value "0R")
      (footprint "eagle-import:R0402")
      (libsource (lib "eagle-import") (part "RES-0402"))
    )
    (comp (ref "R42")
      (value "NC")
      (footprint "eagle-import:R0402")
      (libsource (lib "eagle-import") (part "RES-0402"))
    )
    (comp (ref "R43")
      (value "NC")
      (footprint "eagle-import:R0402")
      (libsource (lib "eagle-import") (part "RES-0402"))
    )
    (comp (ref "R44")
      (value "NC")
      (footprint "eagle-import:R0402")
      (libsource (lib "eagle-import") (part "RES-0402"))
    )
    (comp (ref "R45")
      (value "47K")
      (footprint "eagle-import:R0402")
      (libsource (lib "eagle-import") (part "RES-0402"))
    )
    (comp (ref "R46")
      (value "4.7K")
      (footprint "eagle-import:R0402")
      (libsource (lib "eagle-import") (part "RES-0402"))
    )
    (comp (ref "R47")
      (value "4.7K")
      (footprint "eagle-import:R0402")
      (libsource (lib "eagle-import") (part "RES-0402"))
    )
    (comp (ref "R48")
      (value "47K")
      (footprint "eagle-import:R0402")
      (libsource (lib "eagle-import") (part "RES-0402"))
    )
    (comp (ref "R49")
      (value "59K 1%")
      (footprint "eagle-import:R0402")
      (libsource (lib "eagle-import") (part "RES-0402"))
    )
    (comp (ref "R50")
      (value "59K 1%")
      (footprint "eagle-import:R0402")
      (libsource (lib "eagle-import") (part "RES-0402"))
    )
    (comp (ref "R51")
      (value "680R")
      (footprint "eagle-import:R0402")
      (libsource (lib "eagle-import") (part "RES-0402"))
    )
    (comp (ref "R52")
      (value "100K")
      (footprint "eagle-import:R0402")
      (libsource (lib "eagle-import") (part "RES-0402"))
    )
    (comp (ref "R53")
      (value "USB")
      (footprint "eagle-import:R0402")
      (libsource (lib "eagle-import") (part "RES-0402"))
    )
    (comp (ref "R54")
      (value "10R")
      (footprint "eagle-import:R0402")
      (libsource (lib "eagle-import") (part "RES-0402"))
    )
    (comp (ref "R57")
      (value "47K")
      (footprint "eagle-import:R0402")
      (libsource (lib "eagle-import") (part "RES-0402"))
    )
    (comp (ref "R58")
      (value "NC")
      (footprint "eagle-import:R0402")
      (libsource (lib "eagle-import") (part "RES-0402"))
    )
    (comp (ref "U1")
      (value "SX1302IMLTRT")
      (footprint "eagle-import:QFN68-7_7MM")
      (libsource (lib "eagle-import") (part "SX1302IMLTRT"))
    )
    (comp (ref "U2")
      (value "SX1250IMLTRT")
      (footprint "eagle-import:QFN24-4_4MM")
      (libsource (lib "eagle-import") (part "SX1250IMLTRT"))
    )
    (comp (ref "U3")
      (value "SX1250IMLTRT")
      (footprint "eagle-import:QFN24-4_4MM")
      (libsource (lib "eagle-import") (part "SX1250IMLTRT"))
    )
    (comp (ref "U4")
      (value "TA0801A-SAW-868MHZ")
      (footprint "eagle-import:SAW-SMD6-3_3MM")
      (libsource (lib "eagle-import") (part "TA0801A-SAW-868MHZ"))
    )
    (comp (ref "U5")
      (value "TA0801A-SAW-868MHZ")
      (footprint "eagle-import:SAW-SMD6-3_3MM")
      (libsource (lib "eagle-import") (part "TA0801A-SAW-868MHZ"))
    )
    (comp (ref "U6")
      (value "SKY66420-11")
      (footprint "eagle-import:MCM-16-EP(3X3)")
      (libsource (lib "eagle-import") (part "SKY66420-11"))
    )
    (comp (ref "U8")
      (value "SX1261IMLTRT")
      (footprint "eagle-import:QFN24-4_4MM")
      (libsource (lib "eagle-import") (part "SX1261IMLTRT"))
    )
    (comp (ref "U9")
      (value "STM32L412KX")
      (footprint "eagle-import:UFQFPN-32-5_5MM")
      (libsource (lib "eagle-import") (part "STM32L412KX"))
    )
    (comp (ref "U10")
      (value "STTS751")
      (footprint "eagle-import:UDFN-6(2X2)")
      (libsource (lib "eagle-import") (part "STTS751"))
    )
    (comp (ref "U11")
      (value "MT3520B")
      (footprint "eagle-import:IC_SOT23-5")
      (libsource (lib "eagle-import") (part "MT3520B"))
    )
    (comp (ref "U12")
      (value "TA0801A-SAW-868MHZ")
      (footprint "eagle-import:SAW-SMD6-3_3MM")
      (libsource (lib "eagle-import") (part "TA0801A-SAW-868MHZ"))
    )
    (comp (ref "Y1")
      (value "XTAL-32.768KHZ")
      (footprint "eagle-import:XATL-3215-SMD")
      (libsource (lib "eagle-import") (part "XTAL-32.768KHZ"))
    )
    (comp (ref "Y2")
      (value "TCXO-32MHZ")
      (footprint "eagle-import:TXCO-SMD2.0_1.6")
      (libsource (lib "eagle-import") (part "TCXO-32MHZ"))
    )
  )
  (nets
    (net (code "1") (name "/GPIO10") (class "Default")
      (node (ref "R19") (pin "1") (pinfunction "1_1") (pintype "passive"))
      (node (ref "U1") (pin "51") (pinfunction "GPIO[10]_51") (pintype "passive"))
    )
    (net (code "2") (name "/GPIO11") (class "Default")
      (node (ref "R20") (pin "1") (pinfunction "1_1") (pintype "passive"))
      (node (ref "U1") (pin "50") (pinfunction "GPIO[11]_50") (pintype "passive"))
    )
    (net (code "3") (name "/SX1261_DIO3") (class "Default")
      (node (ref "P5") (pin "P$1") (pinfunction "P$1_P$1") (pintype "bidirectional"))
      (node (ref "U8") (pin "6") (pinfunction "DIO3_6") (pintype "bidirectional"))
    )
    (net (code "4") (name "/VR_PA") (class "Default")
      (node (ref "C26") (pin "1") (pinfunction "1_1") (pintype "passive"))
      (node (ref "C27") (pin "1") (pinfunction "1_1") (pintype "passive"))
      (node (ref "L7") (pin "2") (pinfunction "2_2") (pintype "passive"))
      (node (ref "U3") (pin "1") (pinfunction "VR_PA_1") (pintype "bidirectional"))
    )
    (net (code "5") (name "1V2") (class "Default")
      (node (ref "C76") (pin "2") (pinfunction "2_2") (pintype "passive"))
      (node (ref "C77") (pin "2") (pinfunction "2_2") (pintype "passive"))
      (node (ref "C78") (pin "2") (pinfunction "2_2") (pintype "passive"))
      (node (ref "FB3") (pin "1") (pinfunction "1_1") (pintype "passive"))
      (node (ref "L20") (pin "2") (pinfunction "2_2") (pintype "passive"))
      (node (ref "R49") (pin "1") (pinfunction "1_1") (pintype "passive"))
    )
    (net (code "6") (name "3V3_MAIN") (class "Default")
      (node (ref "C62") (pin "2") (pinfunction "2_2") (pintype "passive"))
      (node (ref "C64") (pin "2") (pinfunction "2_2") (pintype "passive"))
      (node (ref "C65") (pin "2") (pinfunction "2_2") (pintype "passive"))
      (node (ref "C68") (pin "2") (pinfunction "2_2") (pintype "passive"))
      (node (ref "C69") (pin "2") (pinfunction "2_2") (pintype "passive"))
      (node (ref "C71") (pin "2") (pinfunction "2_2") (pintype "passive"))
      (node (ref "C72") (pin "2") (pinfunction "2_2") (pintype "passive"))
      (node (ref "C73") (pin "2") (pinfunction "2_2") (pintype "passive"))
      (node (ref "C74") (pin "2") (pinfunction "2_2") (pintype "passive"))
      (node (ref "C75") (pin "2") (pinfunction "2_2") (pintype "passive"))
      (node (ref "FB5") (pin "1") (pinfunction "1_1") (pintype "passive"))
      (node (ref "FB6") (pin "1") (pinfunction "1_1") (pintype "passive"))
      (node (ref "J1") (pin "2") (pinfunction "3V3_2") (pintype "bidirectional"))
      (node (ref "J1") (pin "24") (pinfunction "3V3_24") (pintype "bidirectional"))
      (node (ref "J1") (pin "39") (pinfunction "3V3_39") (pintype "bidirectional"))
      (node (ref "J1") (pin "41") (pinfunction "3V3_41") (pintype "bidirectional"))
      (node (ref "J1") (pin "52") (pinfunction "3V3_52") (pintype "bidirectional"))
      (node (ref "P7") (pin "P$1") (pinfunction "P$1_P$1") (pintype "bidirectional"))
      (node (ref "Q1") (pin "2") (pinfunction "S_2") (pintype "passive"))
      (node (ref "R17") (pin "2") (pinfunction "2_2") (pintype "passive"))
      (node (ref "R44") (pin "2") (pinfunction "2_2") (pintype "passive"))
      (node (ref "R46") (pin "2") (pinfunction "2_2") (pintype "passive"))
      (node (ref "R47") (pin "2") (pinfunction "2_2") (pintype "passive"))
      (node (ref "R48") (pin "2") (pinfunction "2_2") (pintype "passive"))
      (node (ref "R51") (pin "1") (pinfunction "1_1") (pintype "passive"))
      (node (ref "R57") (pin "2") (pinfunction "2_2") (pintype "passive"))
      (node (ref "U10") (pin "3") (pinfunction "VDD_3") (pintype "bidirectional"))
      (node (ref "U11") (pin "1") (pinfunction "EN_1") (pintype "bidirectional"))
      (node (ref "U11") (pin "4") (pinfunction "VIN_4") (pintype "bidirectional"))
      (node (ref "U9") (pin "1") (pinfunction "VDD_1") (pintype "passive"))
      (node (ref "U9") (pin "17") (pinfunction "VDD_17") (pintype "power_in"))
      (node (ref "U9") (pin "5") (pinfunction "VDDA_5") (pintype "power_in"))
    )
    (net (code "7") (name "CONFIG_OK") (class "Default")
      (node (ref "R22") (pin "1") (pinfunction "1_1") (pintype "passive"))
      (node (ref "U1") (pin "66") (pinfunction "GPIO[0]_66") (pintype "passive"))
    )
    (net (code "8") (name "CSD") (class "Default")
      (node (ref "C51") (pin "1") (pinfunction "1_1") (pintype "passive"))
      (node (ref "R33") (pin "2") (pinfunction "2_2") (pintype "passive"))
      (node (ref "U6") (pin "4") (pinfunction "CSD_4") (pintype "input"))
    )
    (net (code "9") (name "D+") (class "Default")
      (node (ref "J1") (pin "38") (pinfunction "38_38") (pintype "bidirectional"))
      (node (ref "P2") (pin "P$1") (pinfunction "P$1_P$1") (pintype "bidirectional"))
      (node (ref "R9") (pin "1") (pinfunction "1_1") (pintype "passive"))
    )
    (net (code "10") (name "D-") (class "Default")
      (node (ref "J1") (pin "36") (pinfunction "36_36") (pintype "bidirectional"))
      (node (ref "P1") (pin "P$1") (pinfunction "P$1_P$1") (pintype "bidirectional"))
      (node (ref "R7") (pin "1") (pinfunction "1_1") (pintype "passive"))
    )
    (net (code "11") (name "GPIO6") (class "Default")
      (node (ref "U1") (pin "57") (pinfunction "GPIO[6]_57") (pintype "passive"))
    )
    (net (code "12") (name "GPIO9") (class "Default")
      (node (ref "U1") (pin "52") (pinfunction "GPIO[9]_52") (pintype "passive"))
    )
    (net (code "13") (name "HOST_CSN") (class "Default")
      (node (ref "P12") (pin "P$1") (pinfunction "P$1_P$1") (pintype "bidirectional"))
      (node (ref "R1") (pin "1") (pinfunction "1_1") (pintype "passive"))
      (node (ref "R13") (pin "1") (pinfunction "1_1") (pintype "passive"))
      (node (ref "U1") (pin "1") (pinfunction "HOST_CSN_1") (pintype "passive"))
      (node (ref "U9") (pin "10") (pinfunction "PA4_10") (pintype "bidirectional"))
    )
    (net (code "14") (name "HOST_MISO") (class "Default")
      (node (ref "P10") (pin "P$1") (pinfunction "P$1_P$1") (pintype "bidirectional"))
      (node (ref "R11") (pin "1") (pinfunction "1_1") (pintype "passive"))
      (node (ref "R2") (pin "2") (pinfunction "2_2") (pintype "passive"))
      (node (ref "R38") (pin "1") (pinfunction "1_1") (pintype "passive"))
      (node (ref "U9") (pin "12") (pinfunction "PA6_12") (pintype "bidirectional"))
    )
    (net (code "15") (name "HOST_MOSI") (class "Default")
      (node (ref "P11") (pin "P$1") (pinfunction "P$1_P$1") (pintype "bidirectional"))
      (node (ref "R12") (pin "1") (pinfunction "1_1") (pintype "passive"))
      (node (ref "U1") (pin "3") (pinfunction "HOST_MOSI_3") (pintype "passive"))
      (node (ref "U8") (pin "17") (pinfunction "MOSI_17") (pintype "bidirectional"))
      (node (ref "U9") (pin "13") (pinfunction "PA7_13") (pintype "bidirectional"))
    )
    (net (code "16") (name "HOST_SCK") (class "Default")
      (node (ref "P9") (pin "P$1") (pinfunction "P$1_P$1") (pintype "bidirectional"))
      (node (ref "R10") (pin "1") (pinfunction "1_1") (pintype "passive"))
      (node (ref "U1") (pin "4") (pinfunction "HOST_SCK_4") (pintype "passive"))
      (node (ref "U8") (pin "18") (pinfunction "SCK_18") (pintype "bidirectional"))
      (node (ref "U9") (pin "11") (pinfunction "PA5_11") (pintype "input"))
    )
    (net (code "17") (name "I2C_SCL") (class "Default")
      (node (ref "J1") (pin "30") (pinfunction "30_30") (pintype "bidirectional"))
      (node (ref "P16") (pin "P$1") (pinfunction "P$1_P$1") (pintype "bidirectional"))
      (node (ref "R47") (pin "1") (pinfunction "1_1") (pintype "passive"))
      (node (ref "U10") (pin "1") (pinfunction "SCL_1") (pintype "passive"))
      (node (ref "U9") (pin "29") (pinfunction "PB6_29") (pintype "bidirectional"))
    )
    (net (code "18") (name "I2C_SDA") (class "Default")
      (node (ref "J1") (pin "32") (pinfunction "32_32") (pintype "bidirectional"))
      (node (ref "P19") (pin "P$1") (pinfunction "P$1_P$1") (pintype "bidirectional"))
      (node (ref "R46") (pin "1") (pinfunction "1_1") (pintype "passive"))
      (node (ref "U10") (pin "6") (pinfunction "SDA_6") (pintype "bidirectional"))
      (node (ref "U9") (pin "30") (pinfunction "PB7_30") (pintype "bidirectional"))
    )
    (net (code "19") (name "MCU_NRESET") (class "Default")
      (node (ref "C80") (pin "2") (pinfunction "2_2") (pintype "passive"))
      (node (ref "P6") (pin "P$1") (pinfunction "P$1_P$1") (pintype "bidirectional"))
      (node (ref "R57") (pin "1") (pinfunction "1_1") (pintype "passive"))
      (node (ref "R58") (pin "1") (pinfunction "1_1") (pintype "passive"))
      (node (ref "U9") (pin "4") (pinfunction "NRST_4") (pintype "bidirectional"))
    )
    (net (code "20") (name "Net-(ANT1-SIGNAL)") (class "Default")
      (node (ref "ANT1") (pin "1") (pinfunction "SIGNAL_1") (pintype "bidirectional"))
      (node (ref "C47") (pin "1") (pinfunction "1_1") (pintype "passive"))
      (node (ref "D8") (pin "1") (pinfunction "1_1") (pintype "bidirectional"))
    )
    (net (code "21") (name "Net-(ANT2-SIGNAL)") (class "Default")
      (node (ref "ANT2") (pin "1") (pinfunction "SIGNAL_1") (pintype "bidirectional"))
      (node (ref "C50") (pin "1") (pinfunction "1_1") (pintype "passive"))
      (node (ref "D6") (pin "1") (pinfunction "1_1") (pintype "bidirectional"))
    )
    (net (code "22") (name "Net-(C15-Pad1)") (class "Default")
      (node (ref "C15") (pin "1") (pinfunction "1_1") (pintype "passive"))
      (node (ref "R26") (pin "1") (pinfunction "1_1") (pintype "passive"))
    )
    (net (code "23") (name "Net-(C21-Pad1)") (class "Default")
      (node (ref "C21") (pin "1") (pinfunction "1_1") (pintype "passive"))
      (node (ref "R28") (pin "1") (pinfunction "1_1") (pintype "passive"))
    )
    (net (code "24") (name "Net-(C28-Pad1)") (class "Default")
      (node (ref "C28") (pin "1") (pinfunction "1_1") (pintype "passive"))
      (node (ref "C29") (pin "1") (pinfunction "1_1") (pintype "passive"))
      (node (ref "C30") (pin "1") (pinfunction "1_1") (pintype "passive"))
      (node (ref "L8") (pin "2") (pinfunction "2_2") (pintype "passive"))
    )
    (net (code "25") (name "Net-(C30-Pad2)") (class "Default")
      (node (ref "C30") (pin "2") (pinfunction "2_2") (pintype "passive"))
      (node (ref "L9") (pin "1") (pinfunction "1_1") (pintype "passive"))
    )
    (net (code "26") (name "Net-(C40-Pad2)") (class "Default")
      (node (ref "C40") (pin "2") (pinfunction "2_2") (pintype "passive"))
      (node (ref "C41") (pin "2") (pinfunction "2_2") (pintype "passive"))
      (node (ref "L12") (pin "2") (pinfunction "2_2") (pintype "passive"))
      (node (ref "L13") (pin "1") (pinfunction "1_1") (pintype "passive"))
    )
    (net (code "27") (name "Net-(C44-Pad2)") (class "Default")
      (node (ref "C44") (pin "2") (pinfunction "2_2") (pintype "passive"))
      (node (ref "C45") (pin "1") (pinfunction "1_1") (pintype "passive"))
      (node (ref "L14") (pin "2") (pinfunction "2_2") (pintype "passive"))
      (node (ref "L15") (pin "1") (pinfunction "1_1") (pintype "passive"))
    )
    (net (code "28") (name "Net-(C46-Pad2)") (class "Default")
      (node (ref "C46") (pin "2") (pinfunction "2_2") (pintype "passive"))
      (node (ref "C47") (pin "2") (pinfunction "2_2") (pintype "passive"))
      (node (ref "L15") (pin "2") (pinfunction "2_2") (pintype "passive"))
    )
    (net (code "29") (name "Net-(C48-Pad2)") (class "Default")
      (node (ref "C48") (pin "2") (pinfunction "2_2") (pintype "passive"))
      (node (ref "L16") (pin "1") (pinfunction "1_1") (pintype "passive"))
      (node (ref "R32") (pin "2") (pinfunction "2_2") (pintype "passive"))
    )
    (net (code "30") (name "Net-(C49-Pad2)") (class "Default")
      (node (ref "C49") (pin "2") (pinfunction "2_2") (pintype "passive"))
      (node (ref "C50") (pin "2") (pinfunction "2_2") (pintype "passive"))
      (node (ref "L16") (pin "2") (pinfunction "2_2") (pintype "passive"))
    )
    (net (code "31") (name "Net-(C55-Pad1)") (class "Default")
      (node (ref "C55") (pin "1") (pinfunction "1_1") (pintype "passive"))
      (node (ref "R37") (pin "1") (pinfunction "1_1") (pintype "passive"))
    )
    (net (code "32") (name "Net-(C59-Pad1)") (class "Default")
      (node (ref "C59") (pin "1") (pinfunction "1_1") (pintype "passive"))
      (node (ref "C60") (pin "2") (pinfunction "2_2") (pintype "passive"))
      (node (ref "C61") (pin "2") (pinfunction "2_2") (pintype "passive"))
    )
    (net (code "33") (name "Net-(C63-Pad1)") (class "Default")
      (node (ref "C63") (pin "1") (pinfunction "1_1") (pintype "passive"))
      (node (ref "R54") (pin "1") (pinfunction "1_1") (pintype "passive"))
    )
    (net (code "34") (name "Net-(D1-+)") (class "Default")
      (node (ref "D1") (pin "1") (pinfunction "+_1") (pintype "passive"))
      (node (ref "R21") (pin "2") (pinfunction "2_2") (pintype "passive"))
    )
    (net (code "35") (name "Net-(D2-+)") (class "Default")
      (node (ref "D2") (pin "1") (pinfunction "+_1") (pintype "passive"))
      (node (ref "R22") (pin "2") (pinfunction "2_2") (pintype "passive"))
    )
    (net (code "36") (name "Net-(D3-+)") (class "Default")
      (node (ref "D3") (pin "1") (pinfunction "+_1") (pintype "passive"))
      (node (ref "R23") (pin "2") (pinfunction "2_2") (pintype "passive"))
    )
    (net (code "37") (name "Net-(D5-+)") (class "Default")
      (node (ref "D5") (pin "1") (pinfunction "+_1") (pintype "passive"))
      (node (ref "R51") (pin "2") (pinfunction "2_2") (pintype "passive"))
    )
    (net (code "38") (name "Net-(J1-Pad45)") (class "Default")
      (node (ref "J1") (pin "45") (pinfunction "45_45") (pintype "bidirectional"))
      (node (ref "R10") (pin "2") (pinfunction "2_2") (pintype "passive"))
    )
    (net (code "39") (name "Net-(J1-Pad47)") (class "Default")
      (node (ref "J1") (pin "47") (pinfunction "47_47") (pintype "bidirectional"))
      (node (ref "R11") (pin "2") (pinfunction "2_2") (pintype "passive"))
    )
    (net (code "40") (name "Net-(J1-Pad49)") (class "Default")
      (node (ref "J1") (pin "49") (pinfunction "49_49") (pintype "bidirectional"))
      (node (ref "R12") (pin "2") (pinfunction "2_2") (pintype "passive"))
    )
    (net (code "41") (name "Net-(J1-Pad51)") (class "Default")
      (node (ref "J1") (pin "51") (pinfunction "51_51") (pintype "bidirectional"))
      (node (ref "R13") (pin "2") (pinfunction "2_2") (pintype "passive"))
    )
    (net (code "42") (name "Net-(Q1-G)") (class "Default")
      (node (ref "Q1") (pin "1") (pinfunction "G_1") (pintype "passive"))
      (node (ref "Q2") (pin "3") (pinfunction "D_3") (pintype "passive"))
      (node (ref "R17") (pin "1") (pinfunction "1_1") (pintype "passive"))
    )
    (net (code "43") (name "Net-(Q2-G)") (class "Default")
      (node (ref "Q2") (pin "1") (pinfunction "G_1") (pintype "passive"))
      (node (ref "R18") (pin "1") (pinfunction "1_1") (pintype "passive"))
      (node (ref "R52") (pin "1") (pinfunction "1_1") (pintype "passive"))
    )
    (net (code "44") (name "Net-(U1-HOST_MISO)") (class "Default")
      (node (ref "R2") (pin "1") (pinfunction "1_1") (pintype "passive"))
      (node (ref "U1") (pin "2") (pinfunction "HOST_MISO_2") (pintype "passive"))
    )
    (net (code "45") (name "Net-(U1-RADIO_A_CLK_I)") (class "Default")
      (node (ref "R14") (pin "1") (pinfunction "1_1") (pintype "passive"))
      (node (ref "U1") (pin "43") (pinfunction "RADIO_A_CLK_I_43") (pintype "passive"))
    )
    (net (code "46") (name "Net-(U1-RADIO_B_CLK_I)") (class "Default")
      (node (ref "R8") (pin "1") (pinfunction "1_1") (pintype "passive"))
      (node (ref "U1") (pin "34") (pinfunction "RADIO_B_CLK_I_34") (pintype "passive"))
    )
    (net (code "47") (name "Net-(U2-DCC_SW)") (class "Default")
      (node (ref "L1") (pin "2") (pinfunction "2_2") (pintype "passive"))
      (node (ref "U2") (pin "8") (pinfunction "DCC_SW_8") (pintype "bidirectional"))
    )
    (net (code "48") (name "Net-(U2-RFI_N)") (class "Default")
      (node (ref "C19") (pin "2") (pinfunction "2_2") (pintype "passive"))
      (node (ref "L3") (pin "2") (pinfunction "2_2") (pintype "passive"))
      (node (ref "U2") (pin "23") (pinfunction "RFI_N_23") (pintype "bidirectional"))
    )
    (net (code "49") (name "Net-(U2-RFI_P)") (class "Default")
      (node (ref "C18") (pin "2") (pinfunction "2_2") (pintype "passive"))
      (node (ref "L3") (pin "1") (pinfunction "1_1") (pintype "passive"))
      (node (ref "U2") (pin "22") (pinfunction "RFI_P_22") (pintype "bidirectional"))
    )
    (net (code "50") (name "Net-(U2-VDD_IN)") (class "Default")
      (node (ref "C14") (pin "1") (pinfunction "1_1") (pintype "passive"))
      (node (ref "L2") (pin "2") (pinfunction "2_2") (pintype "passive"))
      (node (ref "R25") (pin "1") (pinfunction "1_1") (pintype "passive"))
      (node (ref "U2") (pin "2") (pinfunction "VDD_IN_2") (pintype "bidirectional"))
    )
    (net (code "51") (name "Net-(U2-VREG)") (class "Default")
      (node (ref "C16") (pin "1") (pinfunction "1_1") (pintype "passive"))
      (node (ref "L1") (pin "1") (pinfunction "1_1") (pintype "passive"))
      (node (ref "L2") (pin "1") (pinfunction "1_1") (pintype "passive"))
      (node (ref "U2") (pin "6") (pinfunction "VREG_6") (pintype "bidirectional"))
    )
    (net (code "52") (name "Net-(U2-XTA)") (class "Default")
      (node (ref "C15") (pin "2") (pinfunction "2_2") (pintype "passive"))
      (node (ref "U2") (pin "3") (pinfunction "XTA_3") (pintype "bidirectional"))
    )
    (net (code "53") (name "Net-(U3-DCC_SW)") (class "Default")
      (node (ref "L4") (pin "2") (pinfunction "2_2") (pintype "passive"))
      (node (ref "U3") (pin "8") (pinfunction "DCC_SW_8") (pintype "bidirectional"))
    )
    (net (code "54") (name "Net-(U3-RFI_N)") (class "Default")
      (node (ref "C25") (pin "2") (pinfunction "2_2") (pintype "passive"))
      (node (ref "L6") (pin "2") (pinfunction "2_2") (pintype "passive"))
      (node (ref "U3") (pin "23") (pinfunction "RFI_N_23") (pintype "bidirectional"))
    )
    (net (code "55") (name "Net-(U3-RFI_P)") (class "Default")
      (node (ref "C24") (pin "2") (pinfunction "2_2") (pintype "passive"))
      (node (ref "L6") (pin "1") (pinfunction "1_1") (pintype "passive"))
      (node (ref "U3") (pin "22") (pinfunction "RFI_P_22") (pintype "bidirectional"))
    )
    (net (code "56") (name "Net-(U3-RFO)") (class "Default")
      (node (ref "C28") (pin "2") (pinfunction "2_2") (pintype "passive"))
      (node (ref "L7") (pin "1") (pinfunction "1_1") (pintype "passive"))
      (node (ref "L8") (pin "1") (pinfunction "1_1") (pintype "passive"))
      (node (ref "U3") (pin "24") (pinfunction "RFO_24") (pintype "bidirectional"))
    )
    (net (code "57") (name "Net-(U3-VDD_IN)") (class "Default")
      (node (ref "C20") (pin "1") (pinfunction "1_1") (pintype "passive"))
      (node (ref "L5") (pin "2") (pinfunction "2_2") (pintype "passive"))
      (node (ref "R27") (pin "1") (pinfunction "1_1") (pintype "passive"))
      (node (ref "U3") (pin "2") (pinfunction "VDD_IN_2") (pintype "bidirectional"))
    )
    (net (code "58") (name "Net-(U3-VREG)") (class "Default")
      (node (ref "C22") (pin "1") (pinfunction "1_1") (pintype "passive"))
      (node (ref "L4") (pin "1") (pinfunction "1_1") (pintype "passive"))
      (node (ref "L5") (pin "1") (pinfunction "1_1") (pintype "passive"))
      (node (ref "U3") (pin "6") (pinfunction "VREG_6") (pintype "bidirectional"))
    )
    (net (code "59") (name "Net-(U3-XTA)") (class "Default")
      (node (ref "C21") (pin "2") (pinfunction "2_2") (pintype "passive"))
      (node (ref "U3") (pin "3") (pinfunction "XTA_3") (pintype "bidirectional"))
    )
    (net (code "60") (name "Net-(U4-IN{slash}OUT)") (class "Default")
      (node (ref "C34") (pin "1") (pinfunction "1_1") (pintype "passive"))
      (node (ref "U4") (pin "2") (pinfunction "IN/OUT_2") (pintype "bidirectional"))
    )
    (net (code "61") (name "Net-(U4-OUT{slash}IN)") (class "Default")
      (node (ref "C19") (pin "1") (pinfunction "1_1") (pintype "passive"))
      (node (ref "C25") (pin "1") (pinfunction "1_1") (pintype "passive"))
      (node (ref "C61") (pin "1") (pinfunction "1_1") (pintype "passive"))
      (node (ref "U4") (pin "5") (pinfunction "OUT/IN_5") (pintype "bidirectional"))
    )
    (net (code "62") (name "Net-(U5-IN{slash}OUT)") (class "Default")
      (node (ref "R31") (pin "2") (pinfunction "2_2") (pintype "passive"))
      (node (ref "R32") (pin "1") (pinfunction "1_1") (pintype "passive"))
      (node (ref "U5") (pin "2") (pinfunction "IN/OUT_2") (pintype "bidirectional"))
    )
    (net (code "63") (name "Net-(U5-OUT{slash}IN)") (class "Default")
      (node (ref "U5") (pin "5") (pinfunction "OUT/IN_5") (pintype "bidirectional"))
      (node (ref "U6") (pin "7") (pinfunction "LNA_IN_7") (pintype "passive"))
    )
    (net (code "64") (name "Net-(U6-ANT)") (class "Default")
      (node (ref "C43") (pin "2") (pinfunction "2_2") (pintype "passive"))
      (node (ref "C45") (pin "2") (pinfunction "2_2") (pintype "passive"))
      (node (ref "L14") (pin "1") (pinfunction "1_1") (pintype "passive"))
      (node (ref "U6") (pin "9") (pinfunction "ANT_9") (pintype "passive"))
    )
    (net (code "65") (name "Net-(U6-PA_OUT)") (class "Default")
      (node (ref "L11") (pin "1") (pinfunction "1_1") (pintype "passive"))
      (node (ref "L12") (pin "1") (pinfunction "1_1") (pintype "passive"))
      (node (ref "U6") (pin "13") (pinfunction "PA_OUT_13") (pintype "passive"))
    )
    (net (code "66") (name "Net-(U6-RX)") (class "Default")
      (node (ref "C34") (pin "2") (pinfunction "2_2") (pintype "passive"))
      (node (ref "U6") (pin "2") (pinfunction "RX_2") (pintype "passive"))
    )
    (net (code "67") (name "Net-(U6-RX_FLT)") (class "Default")
      (node (ref "R31") (pin "1") (pinfunction "1_1") (pintype "passive"))
      (node (ref "U6") (pin "8") (pinfunction "RX_FLT_8") (pintype "passive"))
    )
    (net (code "68") (name "Net-(U6-TX)") (class "Default")
      (node (ref "C33") (pin "2") (pinfunction "2_2") (pintype "passive"))
      (node (ref "U6") (pin "1") (pinfunction "TX_1") (pintype "passive"))
    )
    (net (code "69") (name "Net-(U6-TX_IN)") (class "Default")
      (node (ref "C42") (pin "2") (pinfunction "2_2") (pintype "passive"))
      (node (ref "L13") (pin "2") (pinfunction "2_2") (pintype "passive"))
      (node (ref "U6") (pin "11") (pinfunction "TX_IN_11") (pintype "passive"))
    )
    (net (code "70") (name "Net-(U6-VCC1)") (class "Default")
      (node (ref "L10") (pin "1") (pinfunction "1_1") (pintype "passive"))
      (node (ref "U6") (pin "16") (pinfunction "VCC1_16") (pintype "power_in"))
    )
    (net (code "71") (name "Net-(U8-DCC_SW)") (class "Default")
      (node (ref "L18") (pin "2") (pinfunction "2_2") (pintype "passive"))
      (node (ref "U8") (pin "9") (pinfunction "DCC_SW_9") (pintype "bidirectional"))
    )
    (net (code "72") (name "Net-(U8-MISO)") (class "Default")
      (node (ref "R38") (pin "2") (pinfunction "2_2") (pintype "passive"))
      (node (ref "U8") (pin "16") (pinfunction "MISO_16") (pintype "bidirectional"))
    )
    (net (code "73") (name "Net-(U8-NSS)") (class "Default")
      (node (ref "R41") (pin "2") (pinfunction "2_2") (pintype "passive"))
      (node (ref "U8") (pin "19") (pinfunction "NSS_19") (pintype "bidirectional"))
    )
    (net (code "74") (name "Net-(U8-RFI_N)") (class "Default")
      (node (ref "C59") (pin "2") (pinfunction "2_2") (pintype "passive"))
      (node (ref "L19") (pin "2") (pinfunction "2_2") (pintype "passive"))
      (node (ref "U8") (pin "22") (pinfunction "RFI_N_22") (pintype "bidirectional"))
    )
    (net (code "75") (name "Net-(U8-RFI_P)") (class "Default")
      (node (ref "C58") (pin "2") (pinfunction "2_2") (pintype "passive"))
      (node (ref "L19") (pin "1") (pinfunction "1_1") (pintype "passive"))
      (node (ref "U8") (pin "21") (pinfunction "RFI_P_21") (pintype "bidirectional"))
    )
    (net (code "76") (name "Net-(U8-VDD_IN)") (class "Default")
      (node (ref "C54") (pin "1") (pinfunction "1_1") (pintype "passive"))
      (node (ref "L17") (pin "2") (pinfunction "2_2") (pintype "passive"))
      (node (ref "R36") (pin "1") (pinfunction "1_1") (pintype "passive"))
      (node (ref "U8") (pin "1") (pinfunction "VDD_IN_1") (pintype "bidirectional"))
    )
    (net (code "77") (name "Net-(U8-VREG)") (class "Default")
      (node (ref "C56") (pin "1") (pinfunction "1_1") (pintype "passive"))
      (node (ref "L17") (pin "1") (pinfunction "1_1") (pintype "passive"))
      (node (ref "L18") (pin "1") (pinfunction "1_1") (pintype "passive"))
      (node (ref "U8") (pin "7") (pinfunction "VREG_7") (pintype "bidirectional"))
    )
    (net (code "78") (name "Net-(U8-XTA)") (class "Default")
      (node (ref "C55") (pin "2") (pinfunction "2_2") (pintype "passive"))
      (node (ref "U8") (pin "3") (pinfunction "XTA_3") (pintype "bidirectional"))
    )
    (net (code "79") (name "Net-(U9-BOOT)") (class "Default")
      (node (ref "R44") (pin "1") (pinfunction "1_1") (pintype "passive"))
      (node (ref "R45") (pin "2") (pinfunction "2_2") (pintype "passive"))
      (node (ref "U9") (pin "31") (pinfunction "BOOT_31") (pintype "bidirectional"))
    )
    (net (code "80") (name "Net-(U9-PA0-CK_IN)") (class "Default")
      (node (ref "R42") (pin "2") (pinfunction "2_2") (pintype "passive"))
      (node (ref "R43") (pin "1") (pinfunction "1_1") (pintype "passive"))
      (node (ref "U9") (pin "6") (pinfunction "PA0-CK_IN_6") (pintype "bidirectional"))
    )
    (net (code "81") (name "Net-(U9-PC14-OSC32_IN)") (class "Default")
      (node (ref "C66") (pin "2") (pinfunction "2_2") (pintype "passive"))
      (node (ref "U9") (pin "2") (pinfunction "PC14-OSC32_IN_2") (pintype "bidirectional"))
      (node (ref "Y1") (pin "2") (pinfunction "2_2") (pintype "bidirectional"))
    )
    (net (code "82") (name "Net-(U9-PC15-OSC32_OUT)") (class "Default")
      (node (ref "C67") (pin "1") (pinfunction "1_1") (pintype "passive"))
      (node (ref "U9") (pin "3") (pinfunction "PC15-OSC32_OUT_3") (pintype "bidirectional"))
      (node (ref "Y1") (pin "1") (pinfunction "1_1") (pintype "bidirectional"))
    )
    (net (code "83") (name "Net-(U10-\\E\\V\\E\\N\\T\\)") (class "Default")
      (node (ref "R48") (pin "1") (pinfunction "1_1") (pintype "passive"))
      (node (ref "U10") (pin "2") (pinfunction "\\E\\V\\E\\N\\T\\_2") (pintype "passive"))
    )
    (net (code "84") (name "Net-(U11-FB)") (class "Default")
      (node (ref "R49") (pin "2") (pinfunction "2_2") (pintype "passive"))
      (node (ref "R50") (pin "1") (pinfunction "1_1") (pintype "passive"))
      (node (ref "U11") (pin "5") (pinfunction "FB_5") (pintype "bidirectional"))
    )
    (net (code "85") (name "Net-(U11-SW)") (class "Default")
      (node (ref "L20") (pin "1") (pinfunction "1_1") (pintype "passive"))
      (node (ref "U11") (pin "3") (pinfunction "SW_3") (pintype "bidirectional"))
    )
    (net (code "86") (name "Net-(U12-IN{slash}OUT)") (class "Default")
      (node (ref "C31") (pin "1") (pinfunction "1_1") (pintype "passive"))
      (node (ref "L9") (pin "2") (pinfunction "2_2") (pintype "passive"))
      (node (ref "U12") (pin "2") (pinfunction "IN/OUT_2") (pintype "bidirectional"))
    )
    (net (code "87") (name "Net-(U12-OUT{slash}IN)") (class "Default")
      (node (ref "C33") (pin "1") (pinfunction "1_1") (pintype "passive"))
      (node (ref "U12") (pin "5") (pinfunction "OUT/IN_5") (pintype "bidirectional"))
    )
    (net (code "88") (name "Net-(Y2-OUT)") (class "Default")
      (node (ref "R24") (pin "1") (pinfunction "1_1") (pintype "passive"))
      (node (ref "Y2") (pin "3") (pinfunction "OUT_3") (pintype "bidirectional"))
    )
    (net (code "89") (name "Net-(Y2-VCC)") (class "Default")
      (node (ref "C13") (pin "2") (pinfunction "2_2") (pintype "passive"))
      (node (ref "FB1") (pin "2") (pinfunction "2_2") (pintype "passive"))
      (node (ref "Y2") (pin "4") (pinfunction "VCC_4") (pintype "bidirectional"))
    )
    (net (code "90") (name "PA_ON") (class "Default")
      (node (ref "C53") (pin "1") (pinfunction "1_1") (pintype "passive"))
      (node (ref "R35") (pin "2") (pinfunction "2_2") (pintype "passive"))
      (node (ref "U6") (pin "5") (pinfunction "CPS_5") (pintype "input"))
    )
    (net (code "91") (name "POWER_EN") (class "Default")
      (node (ref "U9") (pin "7") (pinfunction "PA1_7") (pintype "bidirectional"))
    )
    (net (code "92") (name "POWER_GND") (class "Default")
      (node (ref "ANT1") (pin "2") (pinfunction "GND_2") (pintype "bidirectional"))
      (node (ref "ANT1") (pin "3") (pinfunction "GND_3") (pintype "bidirectional"))
      (node (ref "ANT2") (pin "2") (pinfunction "GND_2") (pintype "bidirectional"))
      (node (ref "ANT2") (pin "3") (pinfunction "GND_3") (pintype "bidirectional"))
      (node (ref "C1") (pin "1") (pinfunction "1_1") (pintype "passive"))
      (node (ref "C10") (pin "1") (pinfunction "1_1") (pintype "passive"))
      (node (ref "C11") (pin "1") (pinfunction "1_1") (pintype "passive"))
      (node (ref "C12") (pin "1") (pinfunction "1_1") (pintype "passive"))
      (node (ref "C13") (pin "1") (pinfunction "1_1") (pintype "passive"))
      (node (ref "C14") (pin "2") (pinfunction "2_2") (pintype "passive"))
      (node (ref "C16") (pin "2") (pinfunction "2_2") (pintype "passive"))
      (node (ref "C17") (pin "1") (pinfunction "1_1") (pintype "passive"))
      (node (ref "C18") (pin "1") (pinfunction "1_1") (pintype "passive"))
      (node (ref "C2") (pin "1") (pinfunction "1_1") (pintype "passive"))
      (node (ref "C20") (pin "2") (pinfunction "2_2") (pintype "passive"))
      (node (ref "C22") (pin "2") (pinfunction "2_2") (pintype "passive"))
      (node (ref "C23") (pin "1") (pinfunction "1_1") (pintype "passive"))
      (node (ref "C24") (pin "1") (pinfunction "1_1") (pintype "passive"))
      (node (ref "C26") (pin "2") (pinfunction "2_2") (pintype "passive"))
      (node (ref "C27") (pin "2") (pinfunction "2_2") (pintype "passive"))
      (node (ref "C29") (pin "2") (pinfunction "2_2") (pintype "passive"))
      (node (ref "C3") (pin "1") (pinfunction "1_1") (pintype "passive"))
      (node (ref "C31") (pin "2") (pinfunction "2_2") (pintype "passive"))
      (node (ref "C35") (pin "1") (pinfunction "1_1") (pintype "passive"))
      (node (ref "C36") (pin "1") (pinfunction "1_1") (pintype "passive"))
      (node (ref "C37") (pin "1") (pinfunction "1_1") (pintype "passive"))
      (node (ref "C38") (pin "1") (pinfunction "1_1") (pintype "passive"))
      (node (ref "C39") (pin "1") (pinfunction "1_1") (pintype "passive"))
      (node (ref "C4") (pin "1") (pinfunction "1_1") (pintype "passive"))
      (node (ref "C40") (pin "1") (pinfunction "1_1") (pintype "passive"))
      (node (ref "C41") (pin "1") (pinfunction "1_1") (pintype "passive"))
      (node (ref "C42") (pin "1") (pinfunction "1_1") (pintype "passive"))
      (node (ref "C43") (pin "1") (pinfunction "1_1") (pintype "passive"))
      (node (ref "C44") (pin "1") (pinfunction "1_1") (pintype "passive"))
      (node (ref "C46") (pin "1") (pinfunction "1_1") (pintype "passive"))
      (node (ref "C48") (pin "1") (pinfunction "1_1") (pintype "passive"))
      (node (ref "C49") (pin "1") (pinfunction "1_1") (pintype "passive"))
      (node (ref "C5") (pin "1") (pinfunction "1_1") (pintype "passive"))
      (node (ref "C51") (pin "2") (pinfunction "2_2") (pintype "passive"))
      (node (ref "C52") (pin "2") (pinfunction "2_2") (pintype "passive"))
      (node (ref "C53") (pin "2") (pinfunction "2_2") (pintype "passive"))
      (node (ref "C54") (pin "2") (pinfunction "2_2") (pintype "passive"))
      (node (ref "C56") (pin "2") (pinfunction "2_2") (pintype "passive"))
      (node (ref "C57") (pin "1") (pinfunction "1_1") (pintype "passive"))
      (node (ref "C58") (pin "1") (pinfunction "1_1") (pintype "passive"))
      (node (ref "C6") (pin "1") (pinfunction "1_1") (pintype "passive"))
      (node (ref "C60") (pin "1") (pinfunction "1_1") (pintype "passive"))
      (node (ref "C62") (pin "1") (pinfunction "1_1") (pintype "passive"))
      (node (ref "C64") (pin "1") (pinfunction "1_1") (pintype "passive"))
      (node (ref "C65") (pin "1") (pinfunction "1_1") (pintype "passive"))
      (node (ref "C66") (pin "1") (pinfunction "1_1") (pintype "passive"))
      (node (ref "C67") (pin "2") (pinfunction "2_2") (pintype "passive"))
      (node (ref "C68") (pin "1") (pinfunction "1_1") (pintype "passive"))
      (node (ref "C69") (pin "1") (pinfunction "1_1") (pintype "passive"))
      (node (ref "C7") (pin "1") (pinfunction "1_1") (pintype "passive"))
      (node (ref "C71") (pin "1") (pinfunction "1_1") (pintype "passive"))
      (node (ref "C72") (pin "1") (pinfunction "1_1") (pintype "passive"))
      (node (ref "C73") (pin "1") (pinfunction "1_1") (pintype "passive"))
      (node (ref "C74") (pin "1") (pinfunction "1_1") (pintype "passive"))
      (node (ref "C75") (pin "1") (pinfunction "1_1") (pintype "passive"))
      (node (ref "C76") (pin "1") (pinfunction "1_1") (pintype "passive"))
      (node (ref "C77") (pin "1") (pinfunction "1_1") (pintype "passive"))
      (node (ref "C78") (pin "1") (pinfunction "1_1") (pintype "passive"))
      (node (ref "C79") (pin "1") (pinfunction "1_1") (pintype "passive"))
      (node (ref "C8") (pin "1") (pinfunction "1_1") (pintype "passive"))
      (node (ref "C80") (pin "1") (pinfunction "1_1") (pintype "passive"))
      (node (ref "C81") (pin "1") (pinfunction "1_1") (pintype "passive"))
      (node (ref "C82") (pin "1") (pinfunction "1_1") (pintype "passive"))
      (node (ref "C83") (pin "1") (pinfunction "1_1") (pintype "passive"))
      (node (ref "C84") (pin "1") (pinfunction "1_1") (pintype "passive"))
      (node (ref "C9") (pin "1") (pinfunction "1_1") (pintype "passive"))
      (node (ref "D1") (pin "2") (pinfunction "-_2") (pintype "passive"))
      (node (ref "D2") (pin "2") (pinfunction "-_2") (pintype "passive"))
      (node (ref "D3") (pin "2") (pinfunction "-_2") (pintype "passive"))
      (node (ref "D5") (pin "2") (pinfunction "-_2") (pintype "passive"))
      (node (ref "D6") (pin "2") (pinfunction "2_2") (pintype "bidirectional"))
      (node (ref "D8") (pin "2") (pinfunction "2_2") (pintype "bidirectional"))
      (node (ref "J1") (pin "15") (pinfunction "GND_15") (pintype "bidirectional"))
      (node (ref "J1") (pin "18") (pinfunction "GND_18") (pintype "bidirectional"))
      (node (ref "J1") (pin "21") (pinfunction "GND_21") (pintype "bidirectional"))
      (node (ref "J1") (pin "26") (pinfunction "GND_26") (pintype "bidirectional"))
      (node (ref "J1") (pin "27") (pinfunction "GND_27") (pintype "bidirectional"))
      (node (ref "J1") (pin "29") (pinfunction "GND_29") (pintype "bidirectional"))
      (node (ref "J1") (pin "34") (pinfunction "GND_34") (pintype "bidirectional"))
      (node (ref "J1") (pin "35") (pinfunction "GND_35") (pintype "bidirectional"))
      (node (ref "J1") (pin "37") (pinfunction "GND_37") (pintype "bidirectional"))
      (node (ref "J1") (pin "4") (pinfunction "GND_4") (pintype "bidirectional"))
      (node (ref "J1") (pin "40") (pinfunction "GND_40") (pintype "bidirectional"))
      (node (ref "J1") (pin "43") (pinfunction "GND_43") (pintype "bidirectional"))
      (node (ref "J1") (pin "50") (pinfunction "GND_50") (pintype "bidirectional"))
      (node (ref "J1") (pin "9") (pinfunction "GND_9") (pintype "bidirectional"))
      (node (ref "J10") (pin "1") (pinfunction "1_1") (pintype "bidirectional"))
      (node (ref "J10") (pin "2") (pinfunction "2_2") (pintype "bidirectional"))
      (node (ref "J10") (pin "3") (pinfunction "3_3") (pintype "bidirectional"))
      (node (ref "J11") (pin "1") (pinfunction "P$1_1") (pintype "bidirectional"))
      (node (ref "J17") (pin "1") (pinfunction "1_1") (pintype "bidirectional"))
      (node (ref "J17") (pin "2") (pinfunction "2_2") (pintype "bidirectional"))
      (node (ref "J17") (pin "3") (pinfunction "3_3") (pintype "bidirectional"))
      (node (ref "J2") (pin "1") (pinfunction "P$1_1") (pintype "bidirectional"))
      (node (ref "J3") (pin "1") (pinfunction "1_1") (pintype "bidirectional"))
      (node (ref "J3") (pin "2") (pinfunction "2_2") (pintype "bidirectional"))
      (node (ref "J3") (pin "3") (pinfunction "3_3") (pintype "bidirectional"))
      (node (ref "J4") (pin "1") (pinfunction "1_1") (pintype "bidirectional"))
      (node (ref "J4") (pin "2") (pinfunction "2_2") (pintype "bidirectional"))
      (node (ref "J4") (pin "3") (pinfunction "3_3") (pintype "bidirectional"))
      (node (ref "J5") (pin "1") (pinfunction "1_1") (pintype "bidirectional"))
      (node (ref "J5") (pin "2") (pinfunction "2_2") (pintype "bidirectional"))
      (node (ref "J5") (pin "3") (pinfunction "3_3") (pintype "bidirectional"))
      (node (ref "J6") (pin "1") (pinfunction "1_1") (pintype "bidirectional"))
      (node (ref "J6") (pin "2") (pinfunction "2_2") (pintype "bidirectional"))
      (node (ref "J6") (pin "3") (pinfunction "3_3") (pintype "bidirectional"))
      (node (ref "J7") (pin "1") (pinfunction "1_1") (pintype "bidirectional"))
      (node (ref "J7") (pin "2") (pinfunction "2_2") (pintype "bidirectional"))
      (node (ref "J7") (pin "3") (pinfunction "3_3") (pintype "bidirectional"))
      (node (ref "P24") (pin "P$1") (pinfunction "P$1_P$1") (pintype "bidirectional"))
      (node (ref "P8") (pin "P$1") (pinfunction "P$1_P$1") (pintype "bidirectional"))
      (node (ref "Q2") (pin "2") (pinfunction "S_2") (pintype "passive"))
      (node (ref "R15") (pin "1") (pinfunction "1_1") (pintype "passive"))
      (node (ref "R15") (pin "2") (pinfunction "2_2") (pintype "passive"))
      (node (ref "R16") (pin "1") (pinfunction "1_1") (pintype "passive"))
      (node (ref "R16") (pin "2") (pinfunction "2_2") (pintype "passive"))
      (node (ref "R3") (pin "1") (pinfunction "1_1") (pintype "passive"))
      (node (ref "R3") (pin "2") (pinfunction "2_2") (pintype "passive"))
      (node (ref "R43") (pin "2") (pinfunction "2_2") (pintype "passive"))
      (node (ref "R45") (pin "1") (pinfunction "1_1") (pintype "passive"))
      (node (ref "R5") (pin "1") (pinfunction "1_1") (pintype "passive"))
      (node (ref "R50") (pin "2") (pinfunction "2_2") (pintype "passive"))
      (node (ref "R52") (pin "2") (pinfunction "2_2") (pintype "passive"))
      (node (ref "R53") (pin "1") (pinfunction "1_1") (pintype "passive"))
      (node (ref "R53") (pin "2") (pinfunction "2_2") (pintype "passive"))
      (node (ref "U1") (pin "15") (pinfunction "GND_15") (pintype "power_in"))
      (node (ref "U1") (pin "20") (pinfunction "SP_VALID_20") (pintype "passive"))
      (node (ref "U1") (pin "24") (pinfunction "GND_24") (pintype "power_in"))
      (node (ref "U1") (pin "25") (pinfunction "GND_25") (pintype "power_in"))
      (node (ref "U1") (pin "39") (pinfunction "GND_39") (pintype "power_in"))
      (node (ref "U1") (pin "46") (pinfunction "GND_46") (pintype "power_in"))
      (node (ref "U1") (pin "55") (pinfunction "GND_55") (pintype "power_in"))
      (node (ref "U1") (pin "6") (pinfunction "GND_6") (pintype "power_in"))
      (node (ref "U1") (pin "62") (pinfunction "GND_62") (pintype "power_in"))
      (node (ref "U1") (pin "69") (pinfunction "GND_69") (pintype "power_in"))
      (node (ref "U1") (pin "9") (pinfunction "GND_9") (pintype "passive"))
      (node (ref "U10") (pin "4") (pinfunction "ADDR/T\\H\\E\\R\\M\\_4") (pintype "passive"))
      (node (ref "U10") (pin "5") (pinfunction "GND_5") (pintype "bidirectional"))
      (node (ref "U11") (pin "2") (pinfunction "GND_2") (pintype "bidirectional"))
      (node (ref "U12") (pin "1") (pinfunction "GND_1") (pintype "bidirectional"))
      (node (ref "U12") (pin "3") (pinfunction "GND_3") (pintype "bidirectional"))
      (node (ref "U12") (pin "4") (pinfunction "GND_4") (pintype "bidirectional"))
      (node (ref "U12") (pin "6") (pinfunction "GND_6") (pintype "bidirectional"))
      (node (ref "U2") (pin "20") (pinfunction "GND_20") (pintype "bidirectional"))
      (node (ref "U2") (pin "25") (pinfunction "GND_25") (pintype "power_in"))
      (node (ref "U2") (pin "7") (pinfunction "GND_7") (pintype "power_in"))
      (node (ref "U3") (pin "20") (pinfunction "GND_20") (pintype "bidirectional"))
      (node (ref "U3") (pin "25") (pinfunction "GND_25") (pintype "power_in"))
      (node (ref "U3") (pin "7") (pinfunction "GND_7") (pintype "power_in"))
      (node (ref "U4") (pin "1") (pinfunction "GND_1") (pintype "bidirectional"))
      (node (ref "U4") (pin "3") (pinfunction "GND_3") (pintype "bidirectional"))
      (node (ref "U4") (pin "4") (pinfunction "GND_4") (pintype "bidirectional"))
      (node (ref "U4") (pin "6") (pinfunction "GND_6") (pintype "bidirectional"))
      (node (ref "U5") (pin "1") (pinfunction "GND_1") (pintype "bidirectional"))
      (node (ref "U5") (pin "3") (pinfunction "GND_3") (pintype "bidirectional"))
      (node (ref "U5") (pin "4") (pinfunction "GND_4") (pintype "bidirectional"))
      (node (ref "U5") (pin "6") (pinfunction "GND_6") (pintype "bidirectional"))
      (node (ref "U6") (pin "10") (pinfunction "GND_10") (pintype "power_in"))
      (node (ref "U6") (pin "12") (pinfunction "GND_12") (pintype "power_in"))
      (node (ref "U6") (pin "17") (pinfunction "GND_17") (pintype "power_in"))
      (node (ref "U8") (pin "2") (pinfunction "GND_2") (pintype "bidirectional"))
      (node (ref "U8") (pin "20") (pinfunction "GND_20") (pintype "bidirectional"))
      (node (ref "U8") (pin "25") (pinfunction "GND_25") (pintype "bidirectional"))
      (node (ref "U8") (pin "5") (pinfunction "GND_5") (pintype "bidirectional"))
      (node (ref "U8") (pin "8") (pinfunction "GND_8") (pintype "bidirectional"))
      (node (ref "U9") (pin "16") (pinfunction "VSS_16") (pintype "power_in"))
      (node (ref "U9") (pin "32") (pinfunction "VSS_32") (pintype "power_in"))
      (node (ref "U9") (pin "33") (pinfunction "VSS_33") (pintype "power_in"))
      (node (ref "Y2") (pin "1") (pinfunction "GND_1") (pintype "bidirectional"))
      (node (ref "Y2") (pin "2") (pinfunction "GND_2") (pintype "bidirectional"))
    )
    (net (code "93") (name "PPS") (class "Default")
      (node (ref "J1") (pin "19") (pinfunction "19_19") (pintype "bidirectional"))
      (node (ref "P21") (pin "P$1") (pinfunction "P$1_P$1") (pintype "bidirectional"))
      (node (ref "U1") (pin "8") (pinfunction "PPS_8") (pintype "passive"))
      (node (ref "U9") (pin "27") (pinfunction "PB4_27") (pintype "bidirectional"))
    )
    (net (code "94") (name "P_RESET") (class "Default")
      (node (ref "D4") (pin "+") (pinfunction "+_+") (pintype "passive"))
      (node (ref "J1") (pin "22") (pinfunction "22_22") (pintype "bidirectional"))
      (node (ref "P20") (pin "P$1") (pinfunction "P$1_P$1") (pintype "bidirectional"))
      (node (ref "R58") (pin "2") (pinfunction "2_2") (pintype "passive"))
    )
    (net (code "95") (name "RADIO_A_CLK_32M") (class "Default")
      (node (ref "R14") (pin "2") (pinfunction "2_2") (pintype "passive"))
      (node (ref "R42") (pin "1") (pinfunction "1_1") (pintype "passive"))
      (node (ref "U3") (pin "14") (pinfunction "BUSY_14") (pintype "bidirectional"))
    )
    (net (code "96") (name "RADIO_A_CLK_O") (class "Default")
      (node (ref "U1") (pin "48") (pinfunction "RADIO_A_IQ[4]_48") (pintype "passive"))
      (node (ref "U3") (pin "11") (pinfunction "DIO5_11") (pintype "bidirectional"))
    )
    (net (code "97") (name "RADIO_A_CSN") (class "Default")
      (node (ref "U1") (pin "68") (pinfunction "RADIO_A_CSN_68") (pintype "passive"))
      (node (ref "U3") (pin "19") (pinfunction "NSS_19") (pintype "bidirectional"))
    )
    (net (code "98") (name "RADIO_A_IQ0") (class "Default")
      (node (ref "U1") (pin "44") (pinfunction "RADIO_A_IQ[0]_44") (pintype "passive"))
      (node (ref "U3") (pin "13") (pinfunction "DIO1_13") (pintype "bidirectional"))
    )
    (net (code "99") (name "RADIO_A_IQ1") (class "Default")
      (node (ref "U1") (pin "45") (pinfunction "RADIO_A_IQ[1]_45") (pintype "passive"))
      (node (ref "U3") (pin "12") (pinfunction "DIO2_12") (pintype "bidirectional"))
    )
    (net (code "100") (name "RADIO_A_IQ2") (class "Default")
      (node (ref "U1") (pin "49") (pinfunction "RADIO_A_IQ[2]_49") (pintype "passive"))
      (node (ref "U3") (pin "5") (pinfunction "DIO3_5") (pintype "bidirectional"))
    )
    (net (code "101") (name "RADIO_A_IQ3") (class "Default")
      (node (ref "U1") (pin "41") (pinfunction "RADIO_A_IQ[3]_41") (pintype "passive"))
      (node (ref "U3") (pin "21") (pinfunction "DIO4_21") (pintype "bidirectional"))
    )
    (net (code "102") (name "RADIO_A_MISO") (class "Default")
      (node (ref "U1") (pin "42") (pinfunction "RADIO_A_MISO_42") (pintype "passive"))
      (node (ref "U3") (pin "16") (pinfunction "MISO_TX_16") (pintype "bidirectional"))
    )
    (net (code "103") (name "RADIO_A_MOSI") (class "Default")
      (node (ref "U1") (pin "67") (pinfunction "RADIO_A_MOSI_67") (pintype "passive"))
      (node (ref "U3") (pin "17") (pinfunction "MOSI_RX_17") (pintype "bidirectional"))
    )
    (net (code "104") (name "RADIO_A_NRESET") (class "Default")
      (node (ref "U1") (pin "13") (pinfunction "RADIO_CTRL[3]_13") (pintype "passive"))
      (node (ref "U3") (pin "15") (pinfunction "NRESET_15") (pintype "bidirectional"))
    )
    (net (code "105") (name "RADIO_A_SCK") (class "Default")
      (node (ref "U1") (pin "65") (pinfunction "RADIO_A_SCK_65") (pintype "passive"))
      (node (ref "U3") (pin "18") (pinfunction "SCK_18") (pintype "bidirectional"))
    )
    (net (code "106") (name "RADIO_B_CLK_32M") (class "Default")
      (node (ref "R8") (pin "2") (pinfunction "2_2") (pintype "passive"))
      (node (ref "U2") (pin "14") (pinfunction "BUSY_14") (pintype "bidirectional"))
    )
    (net (code "107") (name "RADIO_B_CLK_O") (class "Default")
      (node (ref "U1") (pin "37") (pinfunction "RADIO_B_IQ[4]_37") (pintype "passive"))
      (node (ref "U2") (pin "11") (pinfunction "DIO5_11") (pintype "bidirectional"))
    )
    (net (code "108") (name "RADIO_B_CSN") (class "Default")
      (node (ref "U1") (pin "18") (pinfunction "RADIO_B_CSN_18") (pintype "passive"))
      (node (ref "U2") (pin "19") (pinfunction "NSS_19") (pintype "bidirectional"))
    )
    (net (code "109") (name "RADIO_B_IQ0") (class "Default")
      (node (ref "U1") (pin "35") (pinfunction "RADIO_B_IQ[0]_35") (pintype "passive"))
      (node (ref "U2") (pin "13") (pinfunction "DIO1_13") (pintype "bidirectional"))
    )
    (net (code "110") (name "RADIO_B_IQ1") (class "Default")
      (node (ref "U1") (pin "36") (pinfunction "RADIO_B_IQ[1]_36") (pintype "passive"))
      (node (ref "U2") (pin "12") (pinfunction "DIO2_12") (pintype "bidirectional"))
    )
    (net (code "111") (name "RADIO_B_IQ2") (class "Default")
      (node (ref "U1") (pin "38") (pinfunction "RADIO_B_IQ[2]_38") (pintype "passive"))
      (node (ref "U2") (pin "5") (pinfunction "DIO3_5") (pintype "bidirectional"))
    )
    (net (code "112") (name "RADIO_B_IQ3") (class "Default")
      (node (ref "U1") (pin "32") (pinfunction "RADIO_B_IQ[3]_32") (pintype "passive"))
      (node (ref "U2") (pin "21") (pinfunction "DIO4_21") (pintype "bidirectional"))
    )
    (net (code "113") (name "RADIO_B_MISO") (class "Default")
      (node (ref "U1") (pin "33") (pinfunction "RADIO_B_MISO_33") (pintype "passive"))
      (node (ref "U2") (pin "16") (pinfunction "MISO_TX_16") (pintype "bidirectional"))
    )
    (net (code "114") (name "RADIO_B_MOSI") (class "Default")
      (node (ref "U1") (pin "19") (pinfunction "RADIO_B_MOSI_19") (pintype "passive"))
      (node (ref "U2") (pin "17") (pinfunction "MOSI_RX_17") (pintype "bidirectional"))
    )
    (net (code "115") (name "RADIO_B_NRESET") (class "Default")
      (node (ref "U1") (pin "28") (pinfunction "RADIO_CTRL[9]_28") (pintype "passive"))
      (node (ref "U2") (pin "15") (pinfunction "NRESET_15") (pintype "bidirectional"))
    )
    (net (code "116") (name "RADIO_B_SCK") (class "Default")
      (node (ref "U1") (pin "21") (pinfunction "RADIO_B_SCK_21") (pintype "passive"))
      (node (ref "U2") (pin "18") (pinfunction "SCK_18") (pintype "bidirectional"))
    )
    (net (code "117") (name "RADIO_CTRL1") (class "Default")
      (node (ref "U1") (pin "11") (pinfunction "RADIO_CTRL[1]_11") (pintype "passive"))
    )
    (net (code "118") (name "RXTX_SW") (class "Default")
      (node (ref "C52") (pin "1") (pinfunction "1_1") (pintype "passive"))
      (node (ref "R34") (pin "2") (pinfunction "2_2") (pintype "passive"))
      (node (ref "U6") (pin "6") (pinfunction "CTX_6") (pintype "input"))
    )
    (net (code "119") (name "RX_ON") (class "Default")
      (node (ref "R21") (pin "1") (pinfunction "1_1") (pintype "passive"))
      (node (ref "U1") (pin "59") (pinfunction "GPIO[4]_59") (pintype "passive"))
    )
    (net (code "120") (name "SWCLK") (class "Default")
      (node (ref "P3") (pin "P$1") (pinfunction "P$1_P$1") (pintype "bidirectional"))
      (node (ref "U9") (pin "24") (pinfunction "PA14_24") (pintype "bidirectional"))
    )
    (net (code "121") (name "SWDIO") (class "Default")
      (node (ref "P4") (pin "P$1") (pinfunction "P$1_P$1") (pintype "bidirectional"))
      (node (ref "U9") (pin "23") (pinfunction "PA13_23") (pintype "bidirectional"))
    )
    (net (code "122") (name "SX1261_BUSY") (class "Default")
      (node (ref "J1") (pin "8") (pinfunction "8_8") (pintype "bidirectional"))
      (node (ref "P17") (pin "P$1") (pinfunction "P$1_P$1") (pintype "bidirectional"))
      (node (ref "U8") (pin "14") (pinfunction "BUSY_14") (pintype "bidirectional"))
      (node (ref "U9") (pin "9") (pinfunction "PA3_9") (pintype "bidirectional"))
    )
    (net (code "123") (name "SX1261_DIO1") (class "Default")
      (node (ref "J1") (pin "33") (pinfunction "33_33") (pintype "bidirectional"))
      (node (ref "P15") (pin "P$1") (pinfunction "P$1_P$1") (pintype "bidirectional"))
      (node (ref "U1") (pin "54") (pinfunction "GPIO[7]_54") (pintype "passive"))
      (node (ref "U8") (pin "13") (pinfunction "DIO1_13") (pintype "bidirectional"))
      (node (ref "U9") (pin "15") (pinfunction "PB1_15") (pintype "bidirectional"))
    )
    (net (code "124") (name "SX1261_DIO2") (class "Default")
      (node (ref "J1") (pin "31") (pinfunction "31_31") (pintype "bidirectional"))
      (node (ref "P14") (pin "P$1") (pinfunction "P$1_P$1") (pintype "bidirectional"))
      (node (ref "U8") (pin "12") (pinfunction "DIO2_12") (pintype "bidirectional"))
    )
    (net (code "125") (name "SX1261_NRESET") (class "Default")
      (node (ref "J1") (pin "10") (pinfunction "10_10") (pintype "bidirectional"))
      (node (ref "P18") (pin "P$1") (pinfunction "P$1_P$1") (pintype "bidirectional"))
      (node (ref "R40") (pin "1") (pinfunction "1_1") (pintype "passive"))
      (node (ref "U8") (pin "15") (pinfunction "NRESET_15") (pintype "bidirectional"))
      (node (ref "U9") (pin "18") (pinfunction "PA8_18") (pintype "bidirectional"))
    )
    (net (code "126") (name "SX1261_NSS") (class "Default")
      (node (ref "J1") (pin "25") (pinfunction "25_25") (pintype "bidirectional"))
      (node (ref "P13") (pin "P$1") (pinfunction "P$1_P$1") (pintype "bidirectional"))
      (node (ref "R39") (pin "1") (pinfunction "1_1") (pintype "passive"))
      (node (ref "R41") (pin "1") (pinfunction "1_1") (pintype "passive"))
      (node (ref "U9") (pin "14") (pinfunction "PB0_14") (pintype "bidirectional"))
    )
    (net (code "127") (name "SX1302_CSD") (class "Default")
      (node (ref "R33") (pin "1") (pinfunction "1_1") (pintype "passive"))
      (node (ref "R4") (pin "1") (pinfunction "1_1") (pintype "passive"))
      (node (ref "U1") (pin "10") (pinfunction "RADIO_CTRL[0]_10") (pintype "passive"))
    )
    (net (code "128") (name "SX1302_GPIO8") (class "Default")
      (node (ref "U1") (pin "53") (pinfunction "GPIO[8]_53") (pintype "passive"))
      (node (ref "U9") (pin "26") (pinfunction "PB3_26") (pintype "bidirectional"))
    )
    (net (code "129") (name "SX1302_PA_ON") (class "Default")
      (node (ref "R35") (pin "1") (pinfunction "1_1") (pintype "passive"))
      (node (ref "U1") (pin "16") (pinfunction "RADIO_CTRL[4]_16") (pintype "passive"))
    )
    (net (code "130") (name "SX1302_RESET") (class "Default")
      (node (ref "C63") (pin "2") (pinfunction "2_2") (pintype "passive"))
      (node (ref "D4") (pin "-") (pinfunction "-_-") (pintype "passive"))
      (node (ref "R5") (pin "2") (pinfunction "2_2") (pintype "passive"))
      (node (ref "U1") (pin "7") (pinfunction "RESET_7") (pintype "passive"))
      (node (ref "U9") (pin "8") (pinfunction "PA2_8") (pintype "bidirectional"))
    )
    (net (code "131") (name "SX1302_RXTX_SW") (class "Default")
      (node (ref "R34") (pin "1") (pinfunction "1_1") (pintype "passive"))
      (node (ref "U1") (pin "12") (pinfunction "RADIO_CTRL[2]_12") (pintype "passive"))
    )
    (net (code "132") (name "TCXO_32M_O") (class "Default")
      (node (ref "R24") (pin "2") (pinfunction "2_2") (pintype "passive"))
      (node (ref "R26") (pin "2") (pinfunction "2_2") (pintype "passive"))
      (node (ref "R28") (pin "2") (pinfunction "2_2") (pintype "passive"))
      (node (ref "R37") (pin "2") (pinfunction "2_2") (pintype "passive"))
    )
    (net (code "133") (name "TX_ON") (class "Default")
      (node (ref "R23") (pin "1") (pinfunction "1_1") (pintype "passive"))
      (node (ref "U1") (pin "63") (pinfunction "GPIO[2]_63") (pintype "passive"))
    )
    (net (code "134") (name "USB_D+") (class "Default")
      (node (ref "R9") (pin "2") (pinfunction "2_2") (pintype "passive"))
      (node (ref "U9") (pin "22") (pinfunction "PA12_22") (pintype "bidirectional"))
    )
    (net (code "135") (name "USB_D-") (class "Default")
      (node (ref "R7") (pin "2") (pinfunction "2_2") (pintype "passive"))
      (node (ref "U9") (pin "21") (pinfunction "PA11_21") (pintype "bidirectional"))
    )
    (net (code "136") (name "VCCIO33") (class "Default")
      (node (ref "C10") (pin "2") (pinfunction "2_2") (pintype "passive"))
      (node (ref "C12") (pin "2") (pinfunction "2_2") (pintype "passive"))
      (node (ref "C3") (pin "2") (pinfunction "2_2") (pintype "passive"))
      (node (ref "C4") (pin "2") (pinfunction "2_2") (pintype "passive"))
      (node (ref "C7") (pin "2") (pinfunction "2_2") (pintype "passive"))
      (node (ref "C8") (pin "2") (pinfunction "2_2") (pintype "passive"))
      (node (ref "C83") (pin "2") (pinfunction "2_2") (pintype "passive"))
      (node (ref "C84") (pin "2") (pinfunction "2_2") (pintype "passive"))
      (node (ref "Q1") (pin "3") (pinfunction "D_3") (pintype "passive"))
      (node (ref "R1") (pin "2") (pinfunction "2_2") (pintype "passive"))
      (node (ref "R19") (pin "2") (pinfunction "2_2") (pintype "passive"))
      (node (ref "R20") (pin "2") (pinfunction "2_2") (pintype "passive"))
      (node (ref "R4") (pin "2") (pinfunction "2_2") (pintype "passive"))
      (node (ref "R54") (pin "2") (pinfunction "2_2") (pintype "passive"))
      (node (ref "U1") (pin "14") (pinfunction "VCC_IO_14") (pintype "power_in"))
      (node (ref "U1") (pin "30") (pinfunction "VCC_IO_30") (pintype "power_in"))
      (node (ref "U1") (pin "47") (pinfunction "VCC_IO_47") (pintype "power_in"))
      (node (ref "U1") (pin "61") (pinfunction "VCC_IO_61") (pintype "power_in"))
    )
    (net (code "137") (name "VCC_FEM") (class "Default")
      (node (ref "C35") (pin "2") (pinfunction "2_2") (pintype "passive"))
      (node (ref "C36") (pin "2") (pinfunction "2_2") (pintype "passive"))
      (node (ref "C37") (pin "2") (pinfunction "2_2") (pintype "passive"))
      (node (ref "C38") (pin "2") (pinfunction "2_2") (pintype "passive"))
      (node (ref "C39") (pin "2") (pinfunction "2_2") (pintype "passive"))
      (node (ref "C82") (pin "2") (pinfunction "2_2") (pintype "passive"))
      (node (ref "FB6") (pin "2") (pinfunction "2_2") (pintype "passive"))
      (node (ref "L10") (pin "2") (pinfunction "2_2") (pintype "passive"))
      (node (ref "L11") (pin "2") (pinfunction "2_2") (pintype "passive"))
      (node (ref "U6") (pin "15") (pinfunction "VCC0_15") (pintype "power_in"))
    )
    (net (code "138") (name "VCORE12") (class "Default")
      (node (ref "C1") (pin "2") (pinfunction "2_2") (pintype "passive"))
      (node (ref "C11") (pin "2") (pinfunction "2_2") (pintype "passive"))
      (node (ref "C2") (pin "2") (pinfunction "2_2") (pintype "passive"))
      (node (ref "C5") (pin "2") (pinfunction "2_2") (pintype "passive"))
      (node (ref "C6") (pin "2") (pinfunction "2_2") (pintype "passive"))
      (node (ref "C79") (pin "2") (pinfunction "2_2") (pintype "passive"))
      (node (ref "C9") (pin "2") (pinfunction "2_2") (pintype "passive"))
      (node (ref "FB3") (pin "2") (pinfunction "2_2") (pintype "passive"))
      (node (ref "P23") (pin "P$1") (pinfunction "P$1_P$1") (pintype "bidirectional"))
      (node (ref "R18") (pin "2") (pinfunction "2_2") (pintype "passive"))
      (node (ref "U1") (pin "23") (pinfunction "VCC_CORE_23") (pintype "power_in"))
      (node (ref "U1") (pin "40") (pinfunction "VCC_CORE_40") (pintype "power_in"))
      (node (ref "U1") (pin "5") (pinfunction "VCC_CORE_5") (pintype "power_in"))
      (node (ref "U1") (pin "56") (pinfunction "VCC_CORE_56") (pintype "power_in"))
    )
    (net (code "139") (name "VDD_RADIO") (class "Default")
      (node (ref "C17") (pin "2") (pinfunction "2_2") (pintype "passive"))
      (node (ref "C23") (pin "2") (pinfunction "2_2") (pintype "passive"))
      (node (ref "C57") (pin "2") (pinfunction "2_2") (pintype "passive"))
      (node (ref "C81") (pin "2") (pinfunction "2_2") (pintype "passive"))
      (node (ref "FB1") (pin "1") (pinfunction "1_1") (pintype "passive"))
      (node (ref "FB5") (pin "2") (pinfunction "2_2") (pintype "passive"))
      (node (ref "R25") (pin "2") (pinfunction "2_2") (pintype "passive"))
      (node (ref "R27") (pin "2") (pinfunction "2_2") (pintype "passive"))
      (node (ref "R36") (pin "2") (pinfunction "2_2") (pintype "passive"))
      (node (ref "R39") (pin "2") (pinfunction "2_2") (pintype "passive"))
      (node (ref "R40") (pin "2") (pinfunction "2_2") (pintype "passive"))
      (node (ref "U2") (pin "10") (pinfunction "VBAT_DIO_10") (pintype "bidirectional"))
      (node (ref "U2") (pin "9") (pinfunction "VBAT_RF_9") (pintype "bidirectional"))
      (node (ref "U3") (pin "10") (pinfunction "VBAT_DIO_10") (pintype "bidirectional"))
      (node (ref "U3") (pin "9") (pinfunction "VBAT_RF_9") (pintype "bidirectional"))
      (node (ref "U8") (pin "10") (pinfunction "VBAT_10") (pintype "bidirectional"))
      (node (ref "U8") (pin "11") (pinfunction "VBAT_IO_11") (pintype "bidirectional"))
    )
    (net (code "140") (name "unconnected-(J1-1V5-Pad6)") (class "Default")
      (node (ref "J1") (pin "6") (pinfunction "1V5_6") (pintype "bidirectional"))
    )
    (net (code "141") (name "unconnected-(J1-1V5-Pad28)") (class "Default")
      (node (ref "J1") (pin "28") (pinfunction "1V5_28") (pintype "bidirectional"))
    )
    (net (code "142") (name "unconnected-(J1-1V5-Pad48)") (class "Default")
      (node (ref "J1") (pin "48") (pinfunction "1V5_48") (pintype "bidirectional"))
    )
    (net (code "143") (name "unconnected-(J1-Pad1)") (class "Default")
      (node (ref "J1") (pin "1") (pinfunction "1_1") (pintype "bidirectional"))
    )
    (net (code "144") (name "unconnected-(J1-Pad3)") (class "Default")
      (node (ref "J1") (pin "3") (pinfunction "3_3") (pintype "bidirectional"))
    )
    (net (code "145") (name "unconnected-(J1-Pad5)") (class "Default")
      (node (ref "J1") (pin "5") (pinfunction "5_5") (pintype "bidirectional"))
    )
    (net (code "146") (name "unconnected-(J1-Pad7)") (class "Default")
      (node (ref "J1") (pin "7") (pinfunction "7_7") (pintype "bidirectional"))
    )
    (net (code "147") (name "unconnected-(J1-Pad11)") (class "Default")
      (node (ref "J1") (pin "11") (pinfunction "11_11") (pintype "bidirectional"))
    )
    (net (code "148") (name "unconnected-(J1-Pad12)") (class "Default")
      (node (ref "J1") (pin "12") (pinfunction "12_12") (pintype "bidirectional"))
    )
    (net (code "149") (name "unconnected-(J1-Pad13)") (class "Default")
      (node (ref "J1") (pin "13") (pinfunction "13_13") (pintype "bidirectional"))
    )
    (net (code "150") (name "unconnected-(J1-Pad14)") (class "Default")
      (node (ref "J1") (pin "14") (pinfunction "14_14") (pintype "bidirectional"))
    )
    (net (code "151") (name "unconnected-(J1-Pad16)") (class "Default")
      (node (ref "J1") (pin "16") (pinfunction "16_16") (pintype "bidirectional"))
    )
    (net (code "152") (name "unconnected-(J1-Pad17)") (class "Default")
      (node (ref "J1") (pin "17") (pinfunction "17_17") (pintype "bidirectional"))
    )
    (net (code "153") (name "unconnected-(J1-Pad20)") (class "Default")
      (node (ref "J1") (pin "20") (pinfunction "20_20") (pintype "bidirectional"))
    )
    (net (code "154") (name "unconnected-(J1-Pad23)") (class "Default")
      (node (ref "J1") (pin "23") (pinfunction "23_23") (pintype "bidirectional"))
    )
    (net (code "155") (name "unconnected-(J1-Pad42)") (class "Default")
      (node (ref "J1") (pin "42") (pinfunction "42_42") (pintype "bidirectional"))
    )
    (net (code "156") (name "unconnected-(J1-Pad44)") (class "Default")
      (node (ref "J1") (pin "44") (pinfunction "44_44") (pintype "bidirectional"))
    )
    (net (code "157") (name "unconnected-(J1-Pad46)") (class "Default")
      (node (ref "J1") (pin "46") (pinfunction "46_46") (pintype "bidirectional"))
    )
    (net (code "158") (name "unconnected-(U1-GPIO[1]-Pad64)") (class "Default")
      (node (ref "U1") (pin "64") (pinfunction "GPIO[1]_64") (pintype "passive"))
    )
    (net (code "159") (name "unconnected-(U1-GPIO[3]-Pad60)") (class "Default")
      (node (ref "U1") (pin "60") (pinfunction "GPIO[3]_60") (pintype "passive"))
    )
    (net (code "160") (name "unconnected-(U1-GPIO[5]-Pad58)") (class "Default")
      (node (ref "U1") (pin "58") (pinfunction "GPIO[5]_58") (pintype "passive"))
    )
    (net (code "161") (name "unconnected-(U1-RADIO_CTRL[5]-Pad17)") (class "Default")
      (node (ref "U1") (pin "17") (pinfunction "RADIO_CTRL[5]_17") (pintype "passive"))
    )
    (net (code "162") (name "unconnected-(U1-RADIO_CTRL[6]-Pad22)") (class "Default")
      (node (ref "U1") (pin "22") (pinfunction "RADIO_CTRL[6]_22") (pintype "passive"))
    )
    (net (code "163") (name "unconnected-(U1-RADIO_CTRL[7]-Pad26)") (class "Default")
      (node (ref "U1") (pin "26") (pinfunction "RADIO_CTRL[7]_26") (pintype "passive"))
    )
    (net (code "164") (name "unconnected-(U1-RADIO_CTRL[8]-Pad27)") (class "Default")
      (node (ref "U1") (pin "27") (pinfunction "RADIO_CTRL[8]_27") (pintype "passive"))
    )
    (net (code "165") (name "unconnected-(U1-RADIO_CTRL[10]-Pad29)") (class "Default")
      (node (ref "U1") (pin "29") (pinfunction "RADIO_CTRL[10]_29") (pintype "passive"))
    )
    (net (code "166") (name "unconnected-(U1-RADIO_CTRL[11]-Pad31)") (class "Default")
      (node (ref "U1") (pin "31") (pinfunction "RADIO_CTRL[11]_31") (pintype "passive"))
    )
    (net (code "167") (name "unconnected-(U2-RFO-Pad24)") (class "Default")
      (node (ref "U2") (pin "24") (pinfunction "RFO_24") (pintype "bidirectional"))
    )
    (net (code "168") (name "unconnected-(U2-VR_PA-Pad1)") (class "Default")
      (node (ref "U2") (pin "1") (pinfunction "VR_PA_1") (pintype "bidirectional"))
    )
    (net (code "169") (name "unconnected-(U2-XTB-Pad4)") (class "Default")
      (node (ref "U2") (pin "4") (pinfunction "XTB_4") (pintype "bidirectional"))
    )
    (net (code "170") (name "unconnected-(U3-XTB-Pad4)") (class "Default")
      (node (ref "U3") (pin "4") (pinfunction "XTB_4") (pintype "bidirectional"))
    )
    (net (code "171") (name "unconnected-(U6-N{slash}C-Pad14)") (class "Default")
      (node (ref "U6") (pin "14") (pinfunction "N/C_14") (pintype "passive"))
    )
    (net (code "172") (name "unconnected-(U6-TX_ALT-Pad3)") (class "Default")
      (node (ref "U6") (pin "3") (pinfunction "TX_ALT_3") (pintype "passive"))
    )
    (net (code "173") (name "unconnected-(U8-RFO-Pad23)") (class "Default")
      (node (ref "U8") (pin "23") (pinfunction "RFO_23") (pintype "bidirectional"))
    )
    (net (code "174") (name "unconnected-(U8-VR_PA-Pad24)") (class "Default")
      (node (ref "U8") (pin "24") (pinfunction "VR_PA_24") (pintype "bidirectional"))
    )
    (net (code "175") (name "unconnected-(U8-XTB-Pad4)") (class "Default")
      (node (ref "U8") (pin "4") (pinfunction "XTB_4") (pintype "bidirectional"))
    )
    (net (code "176") (name "unconnected-(U9-PA9-Pad19)") (class "Default")
      (node (ref "U9") (pin "19") (pinfunction "PA9_19") (pintype "bidirectional"))
    )
    (net (code "177") (name "unconnected-(U9-PA10-Pad20)") (class "Default")
      (node (ref "U9") (pin "20") (pinfunction "PA10_20") (pintype "bidirectional"))
    )
    (net (code "178") (name "unconnected-(U9-PA15-Pad25)") (class "Default")
      (node (ref "U9") (pin "25") (pinfunction "PA15_25") (pintype "bidirectional"))
    )
    (net (code "179") (name "unconnected-(U9-PB5-Pad28)") (class "Default")
      (node (ref "U9") (pin "28") (pinfunction "PB5_28") (pintype "bidirectional"))
    )
  )
)
